# PX4Node_mini_V0_1_1.net
KiCad netlist of a schematic drawn in EAGLE
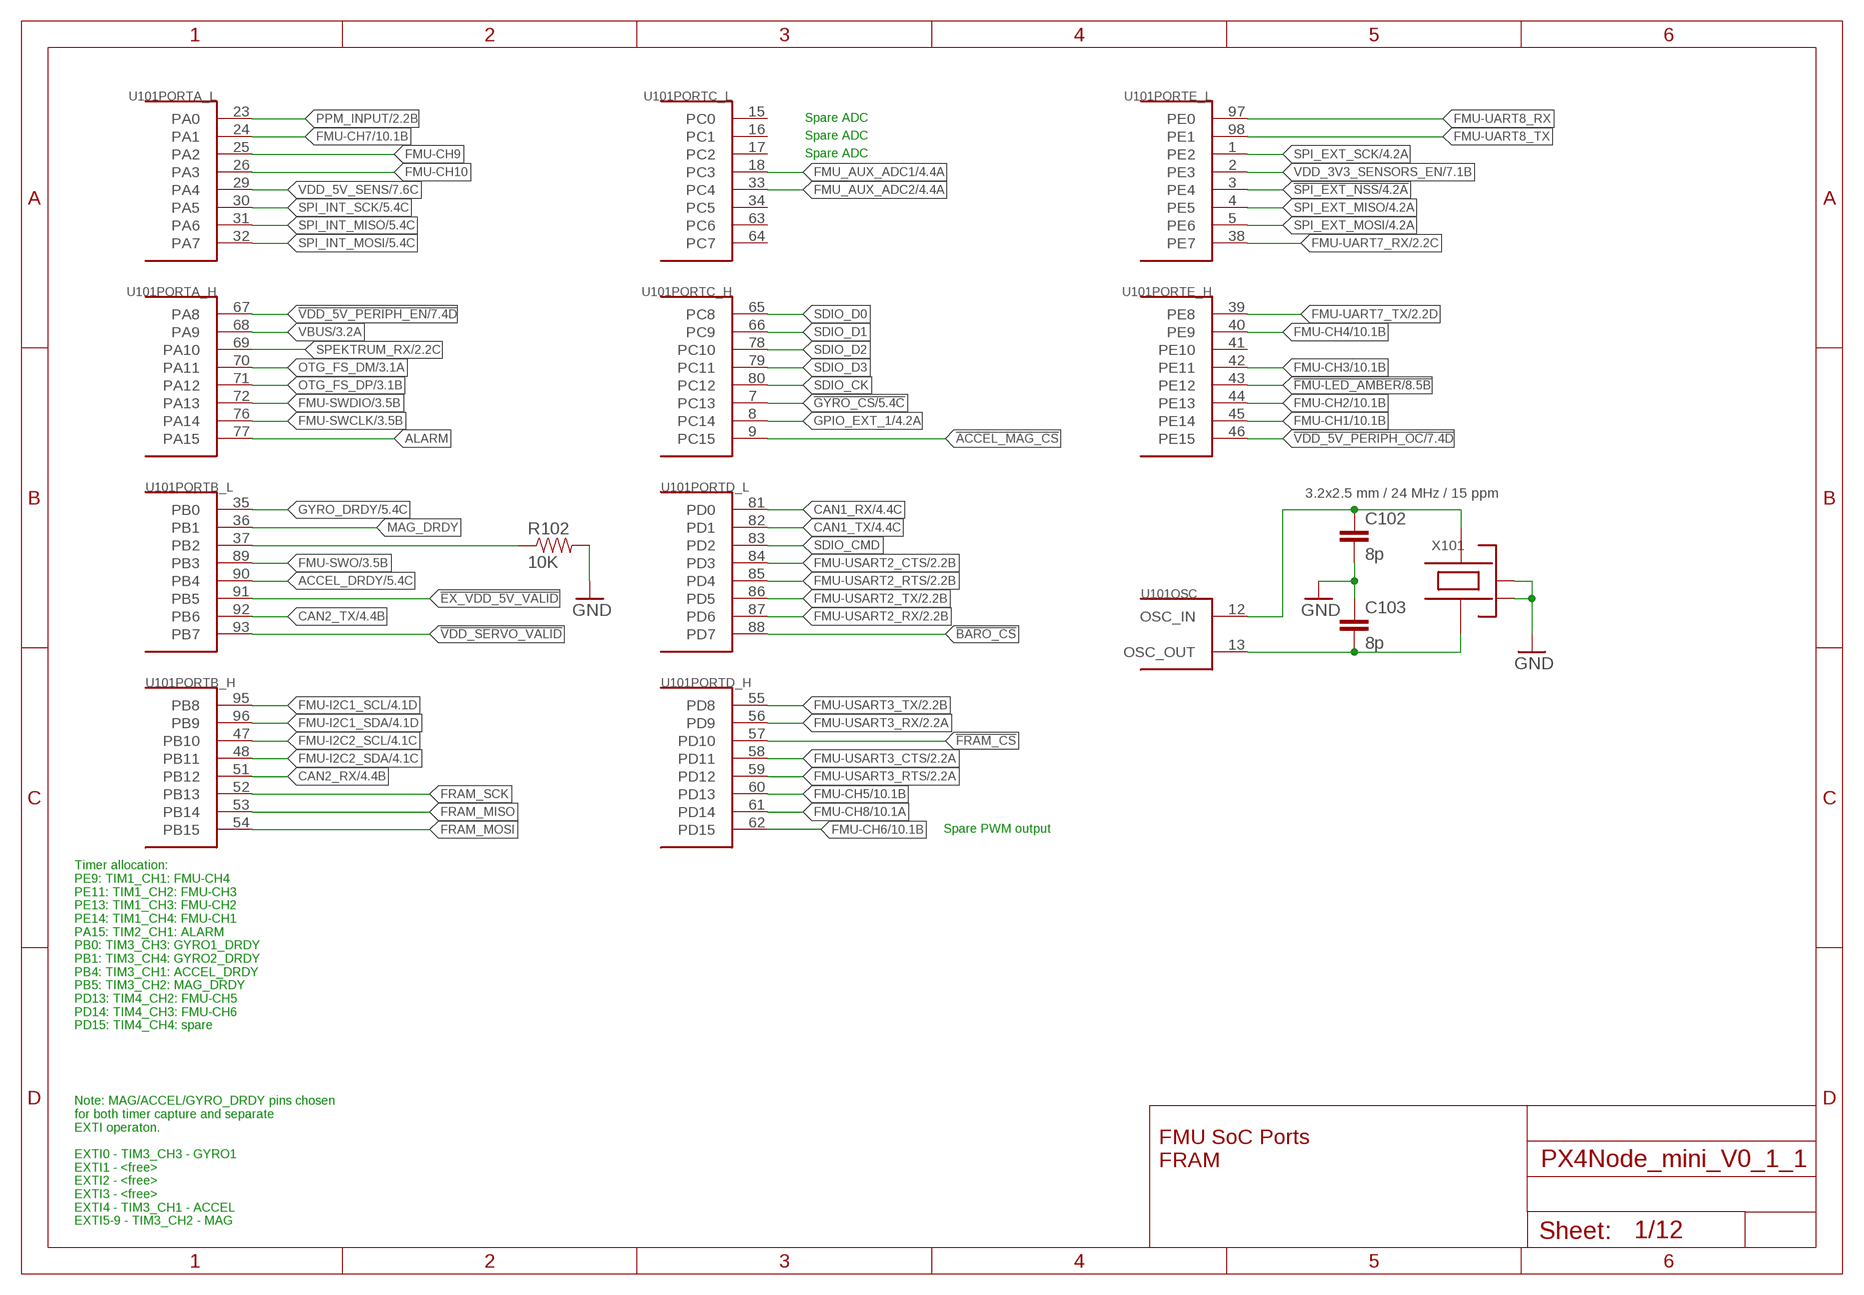
[diagram p0: schematic, sheet 1]
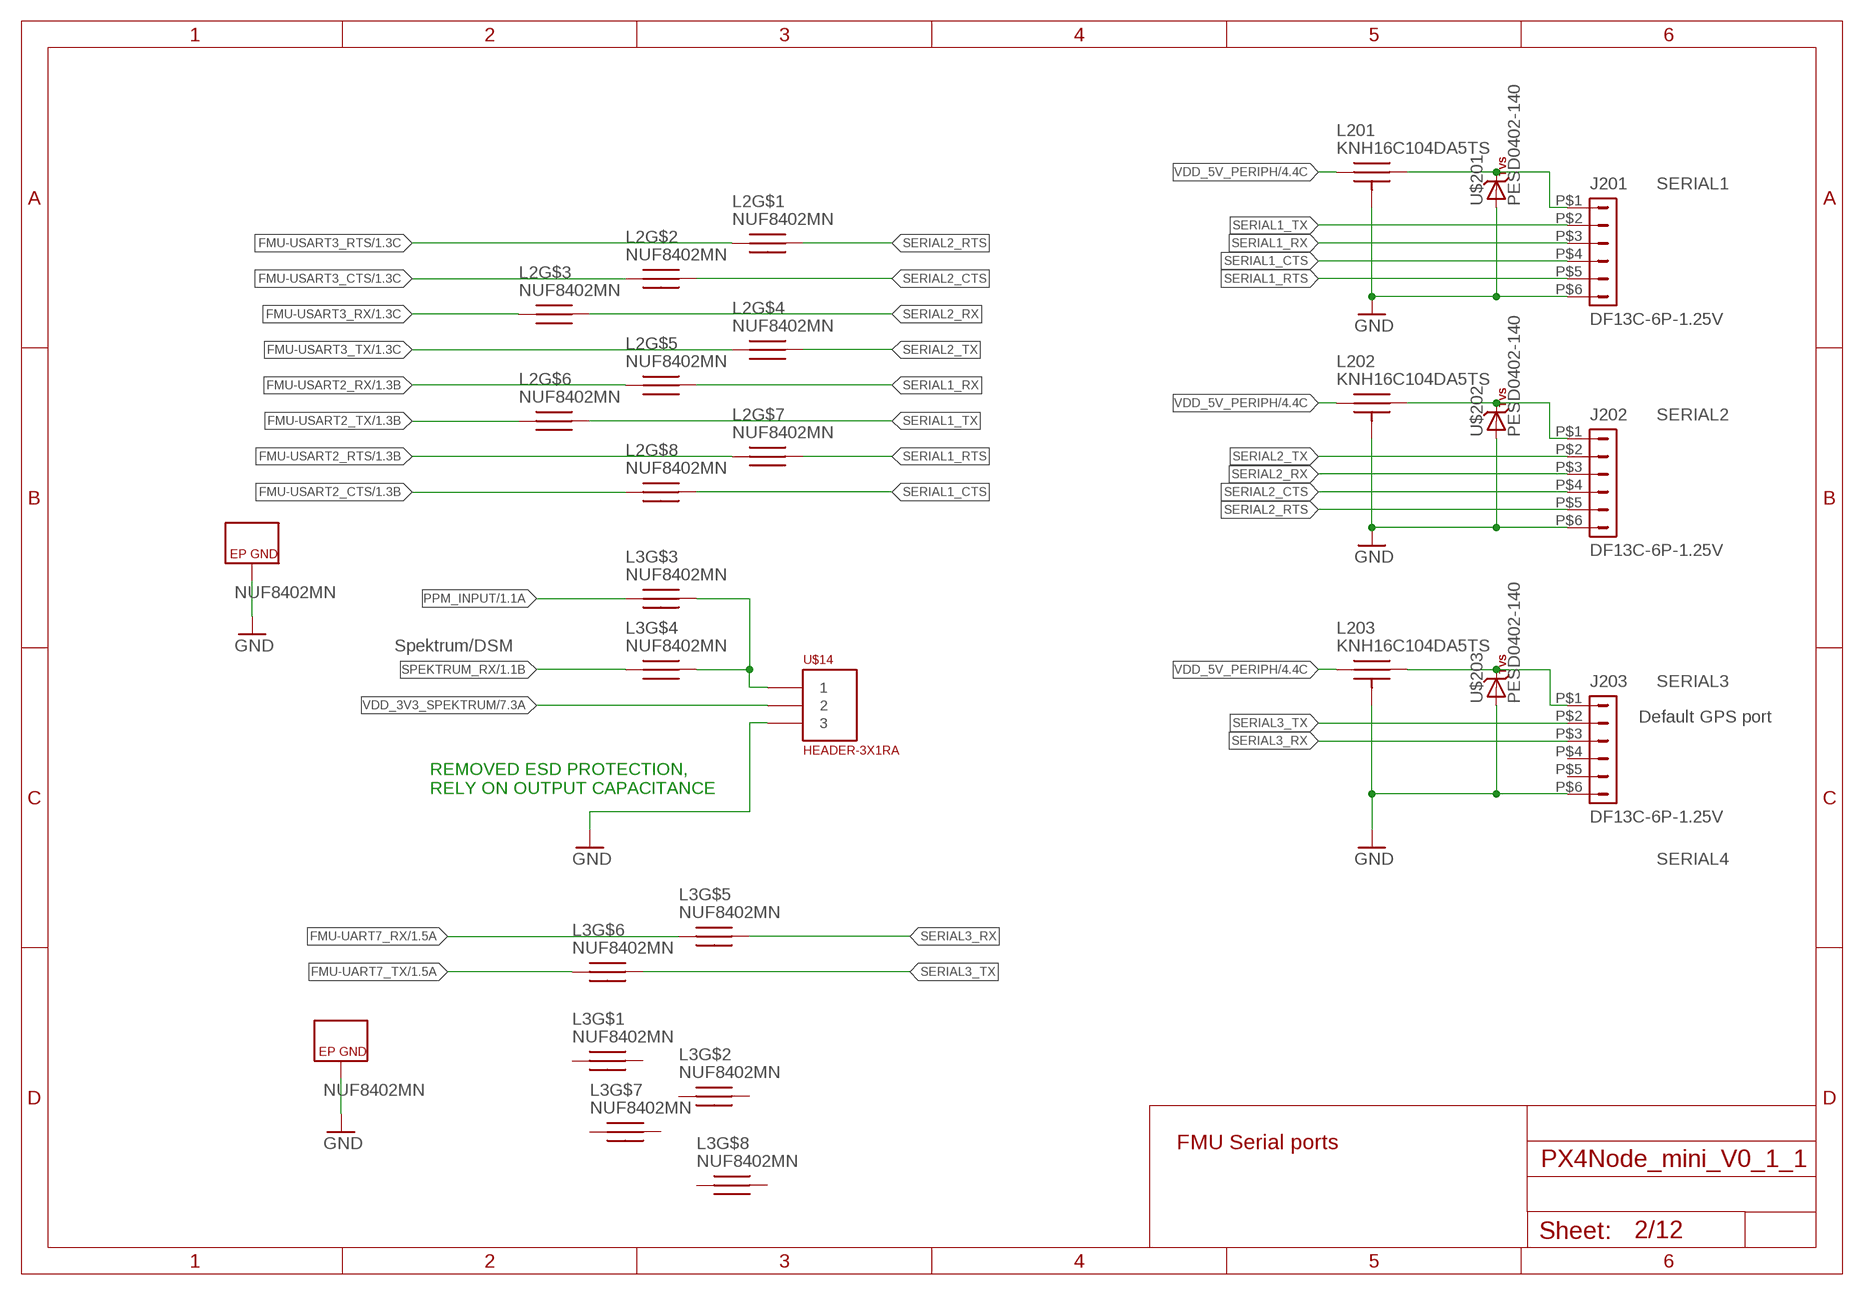
[diagram p1: schematic, sheet 2]
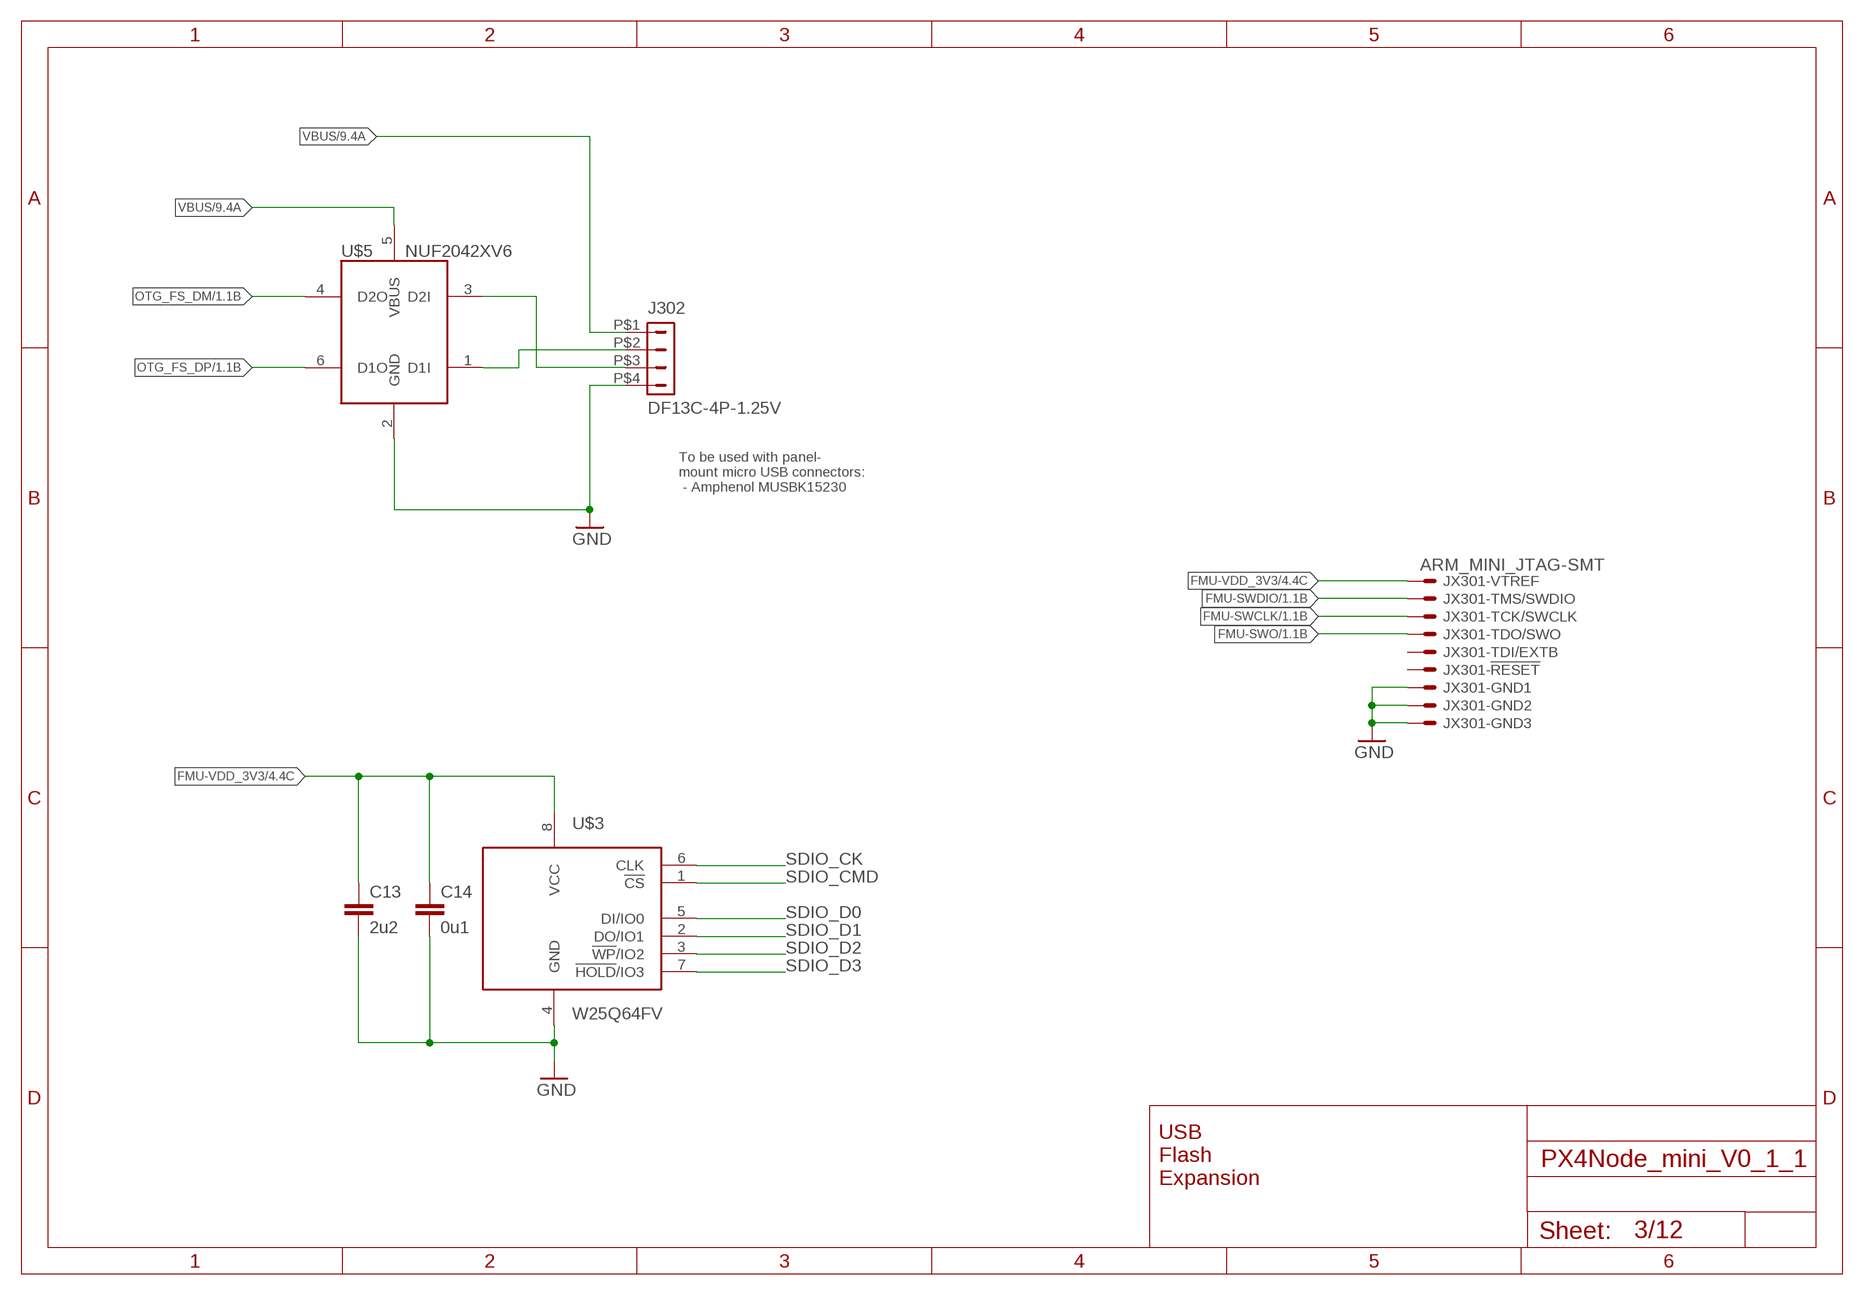
[diagram p2: schematic, sheet 3]
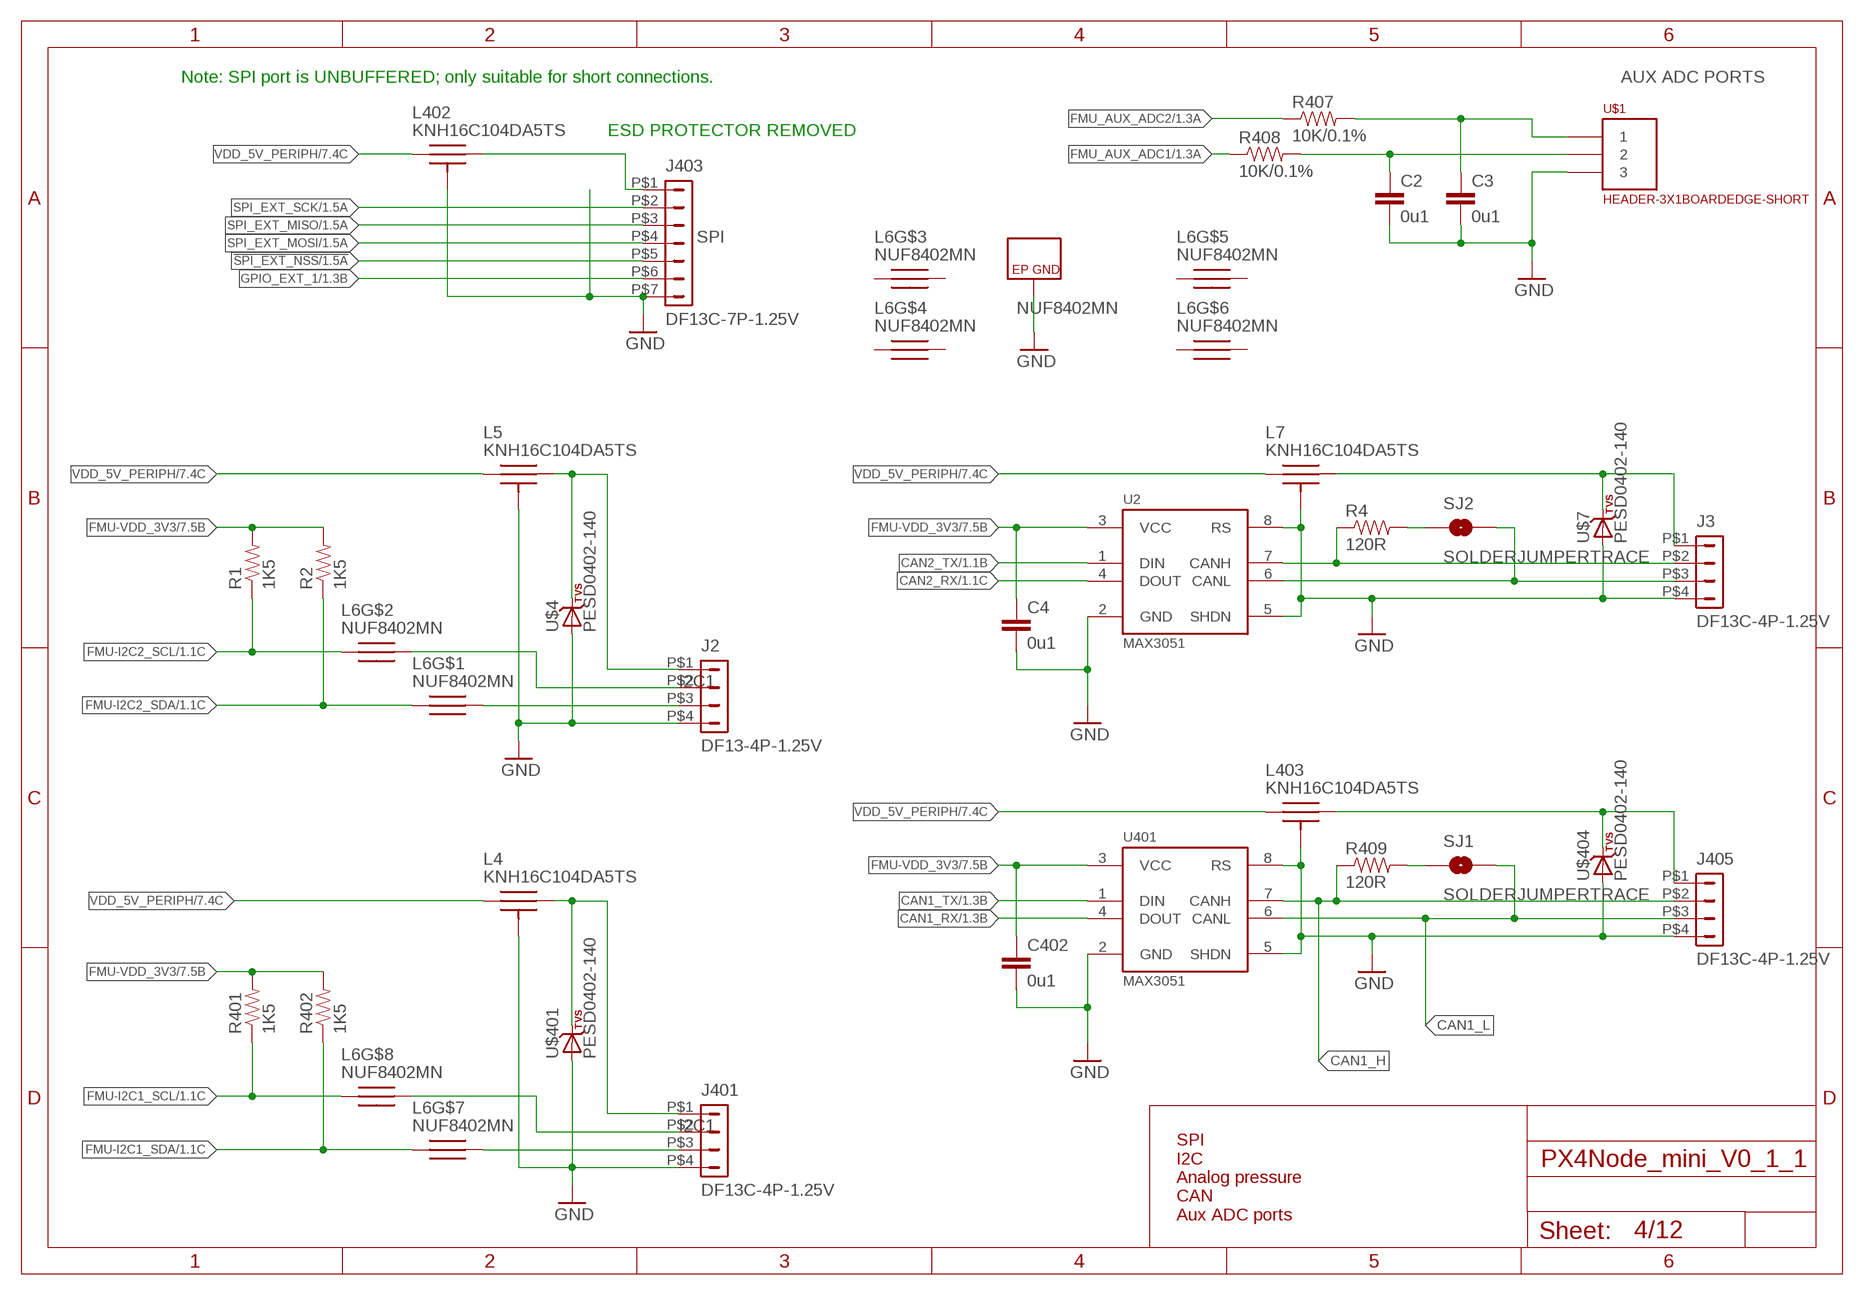
[diagram p3: schematic, sheet 4]
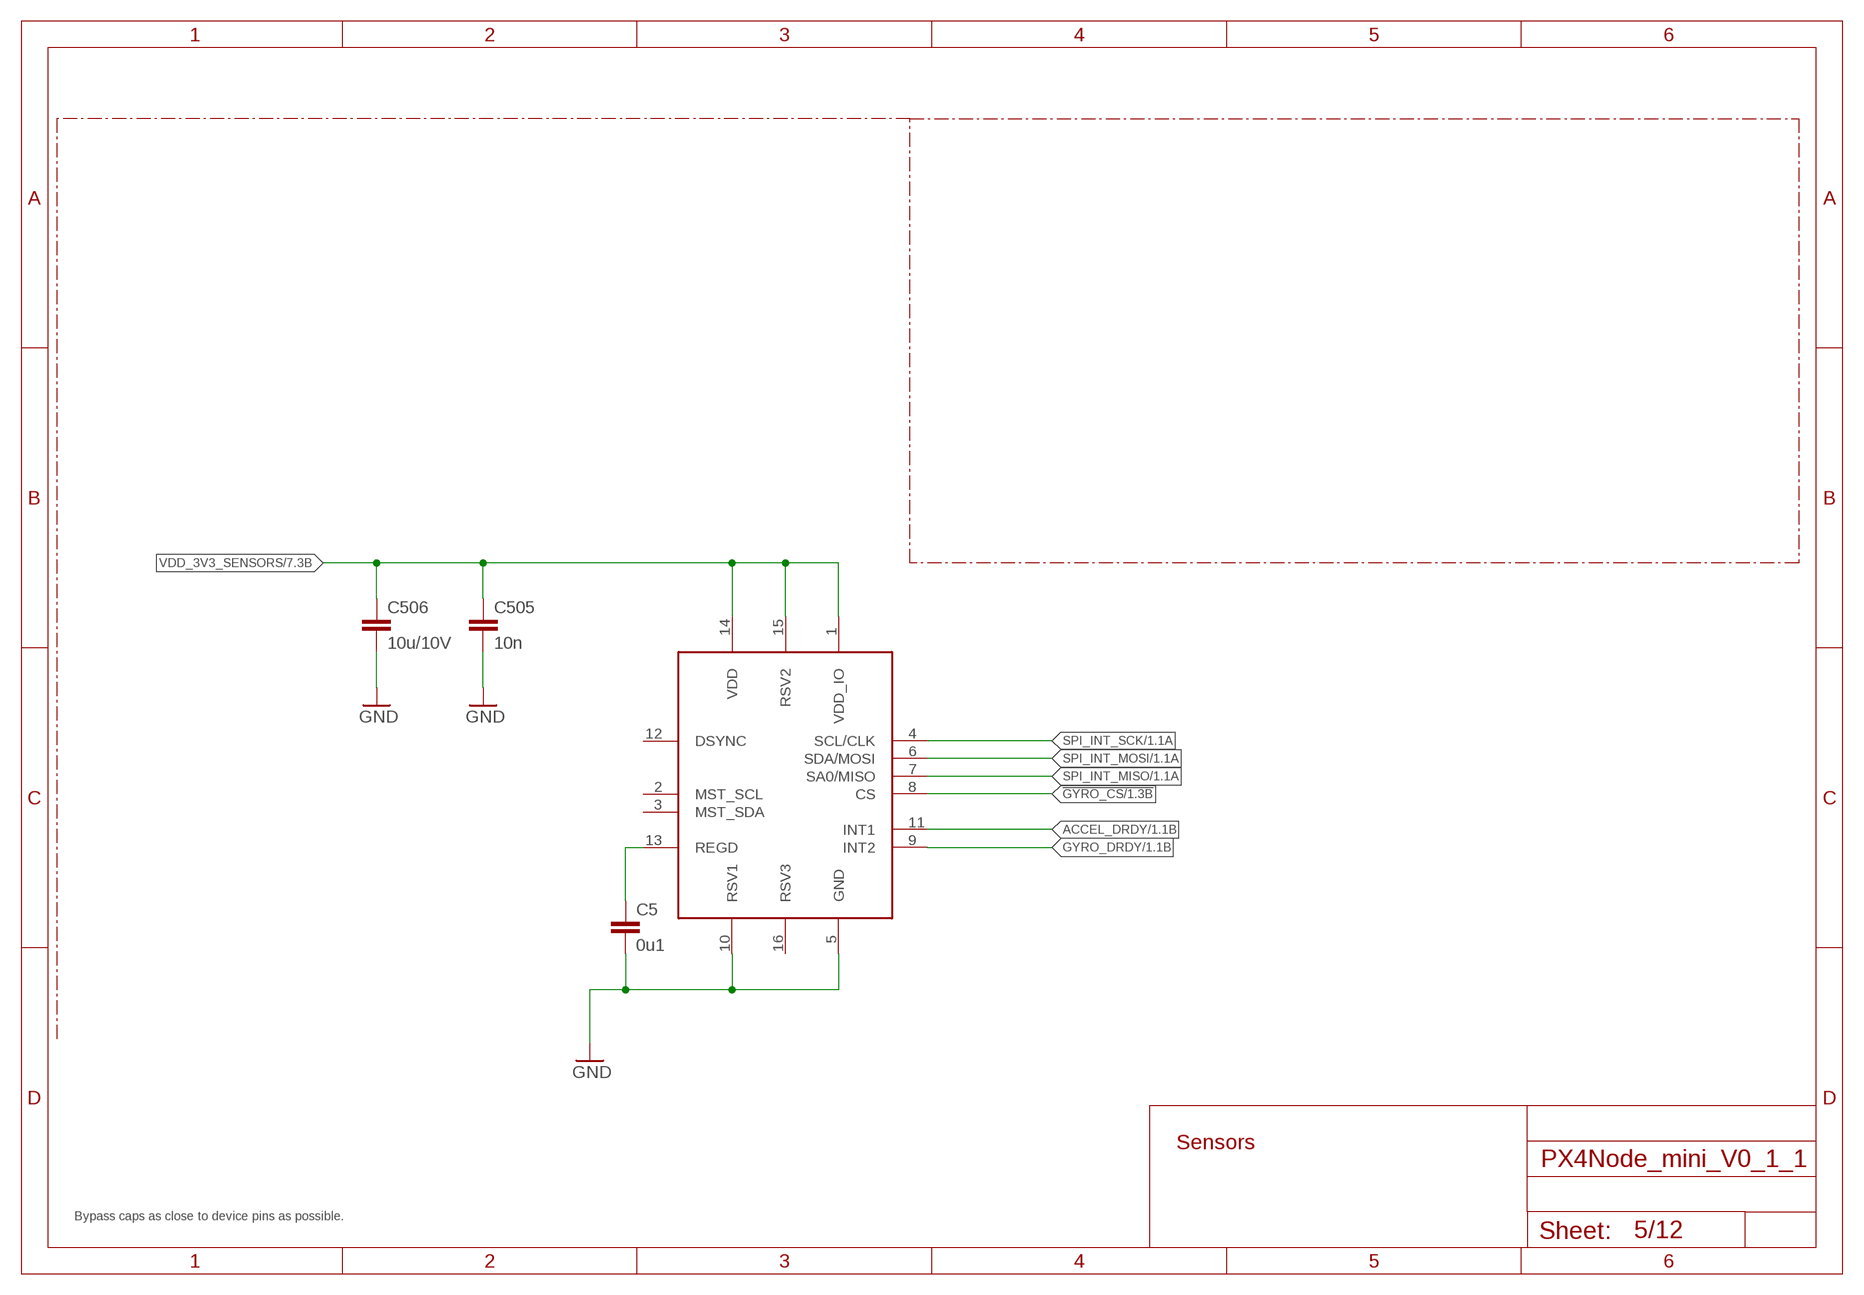
[diagram p4: schematic, sheet 5]
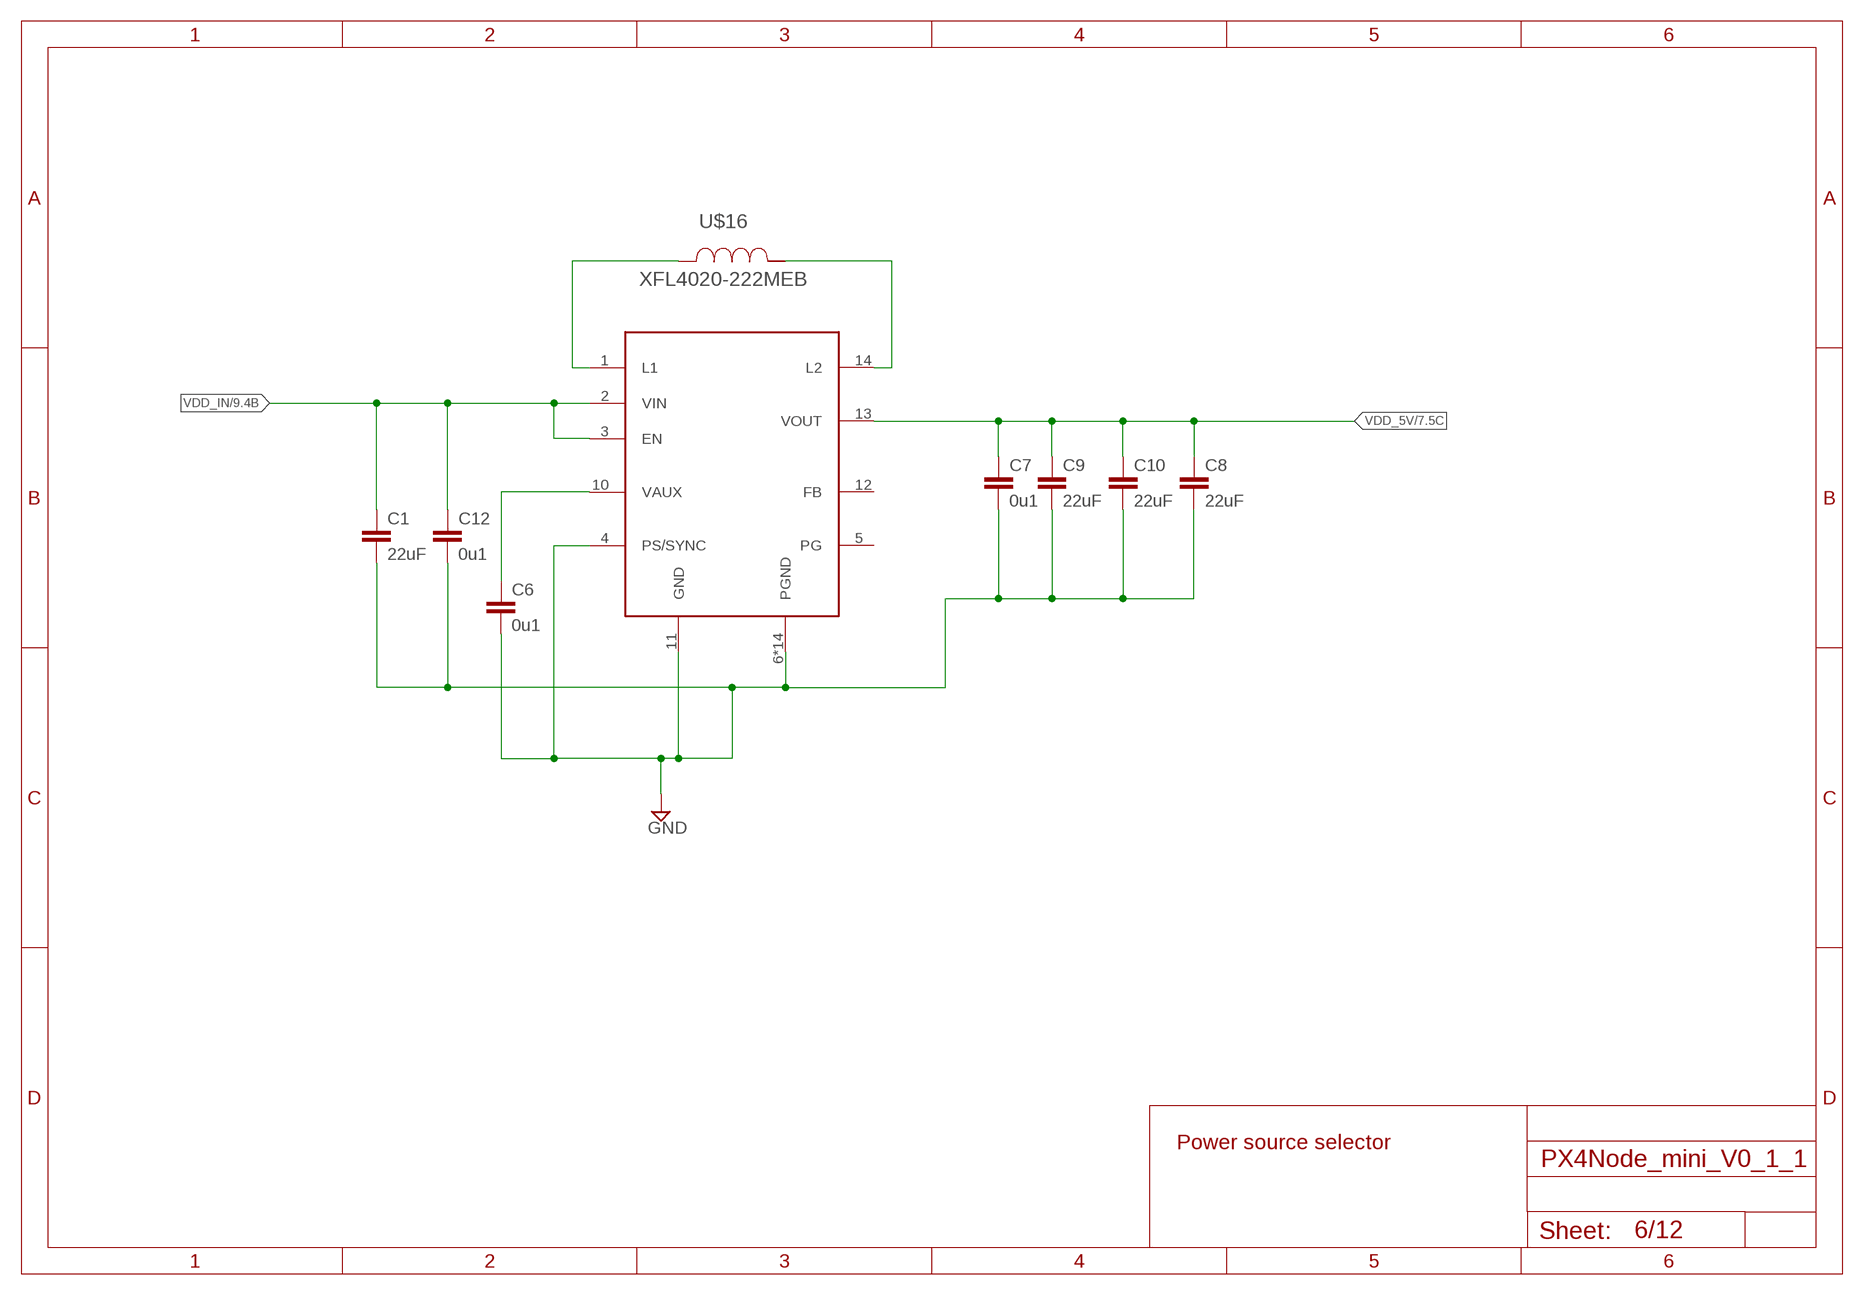
[diagram p5: schematic, sheet 6]
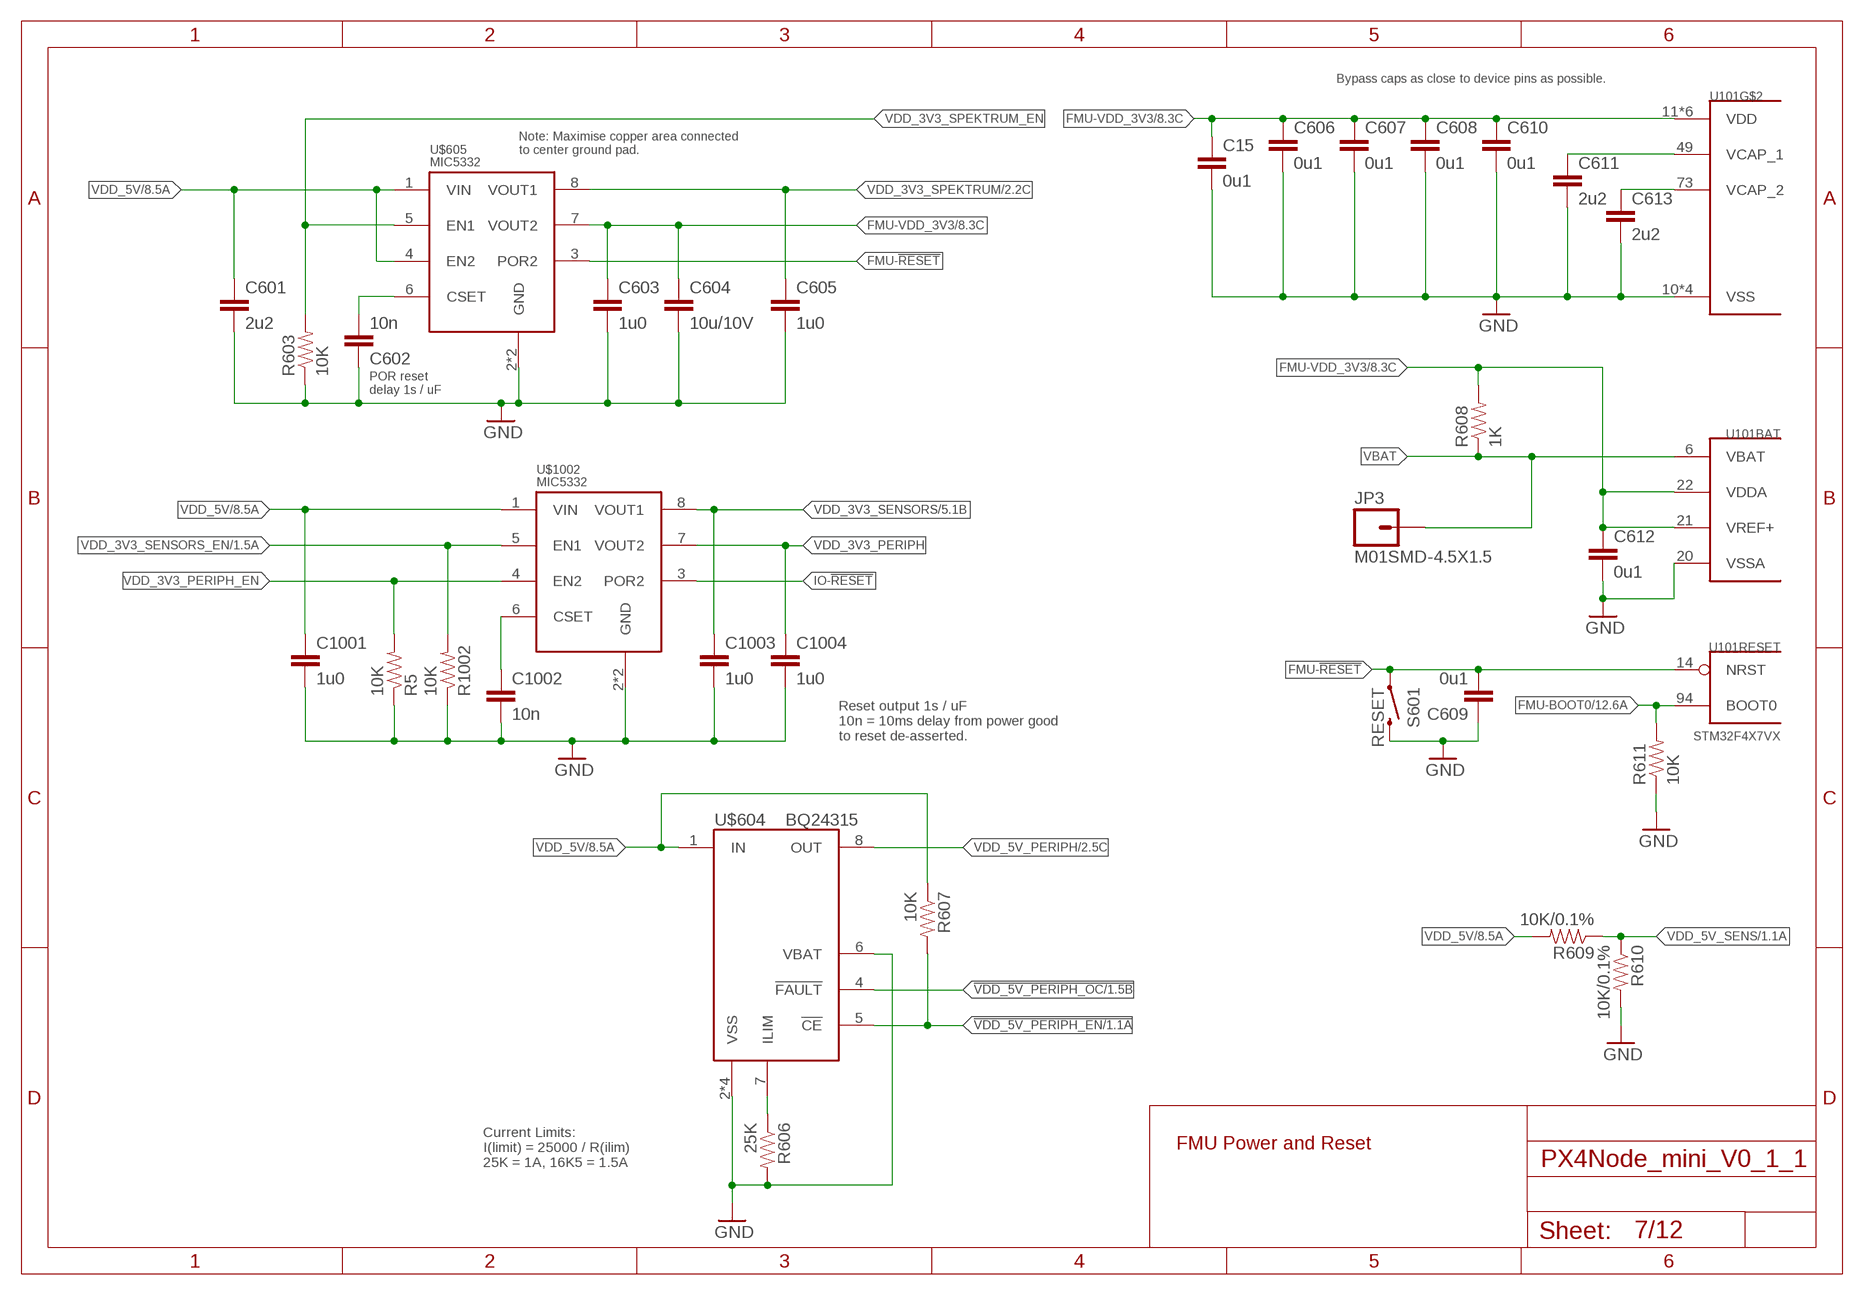
[diagram p6: schematic, sheet 7]
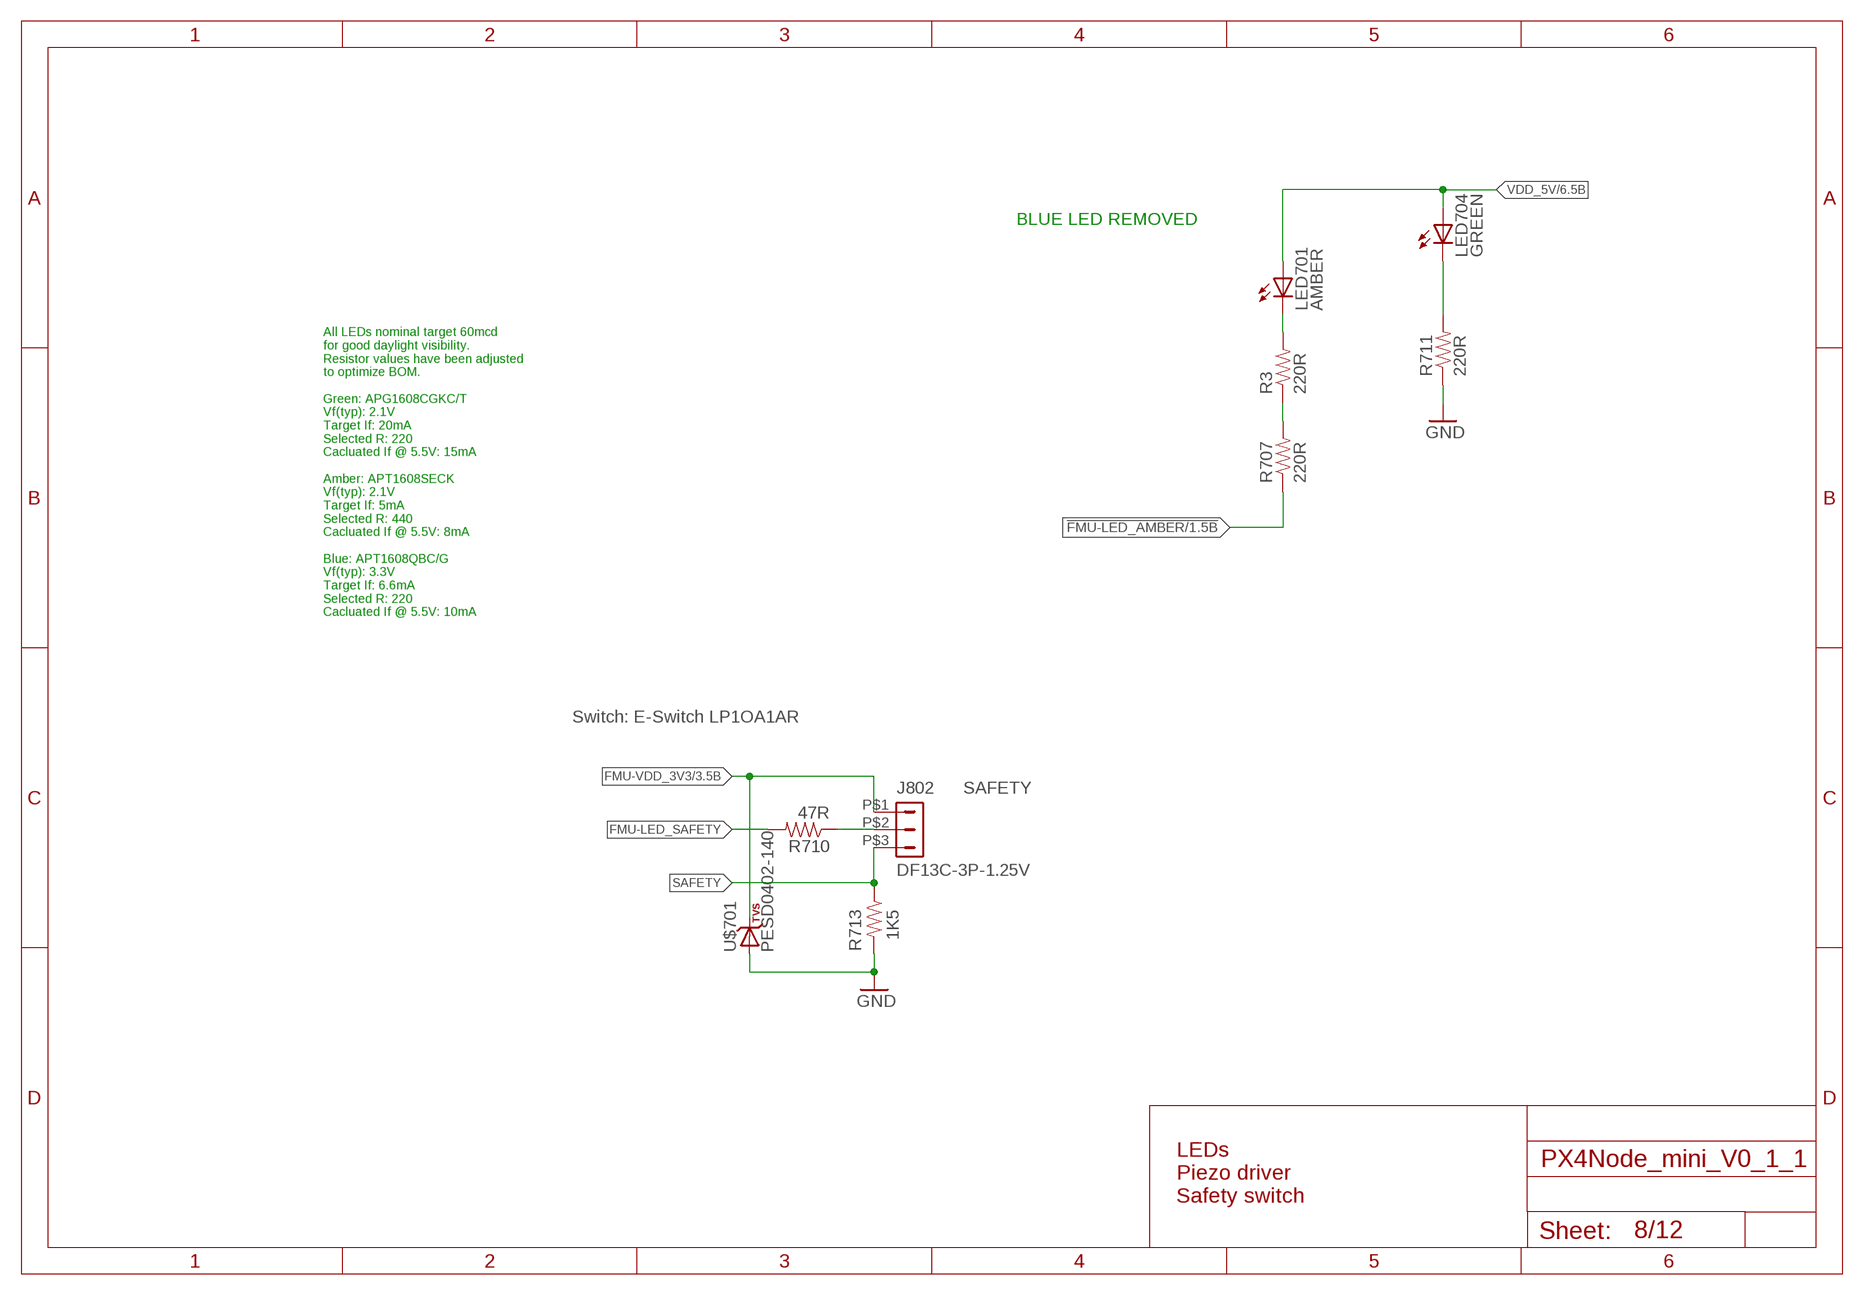
[diagram p7: schematic, sheet 8]
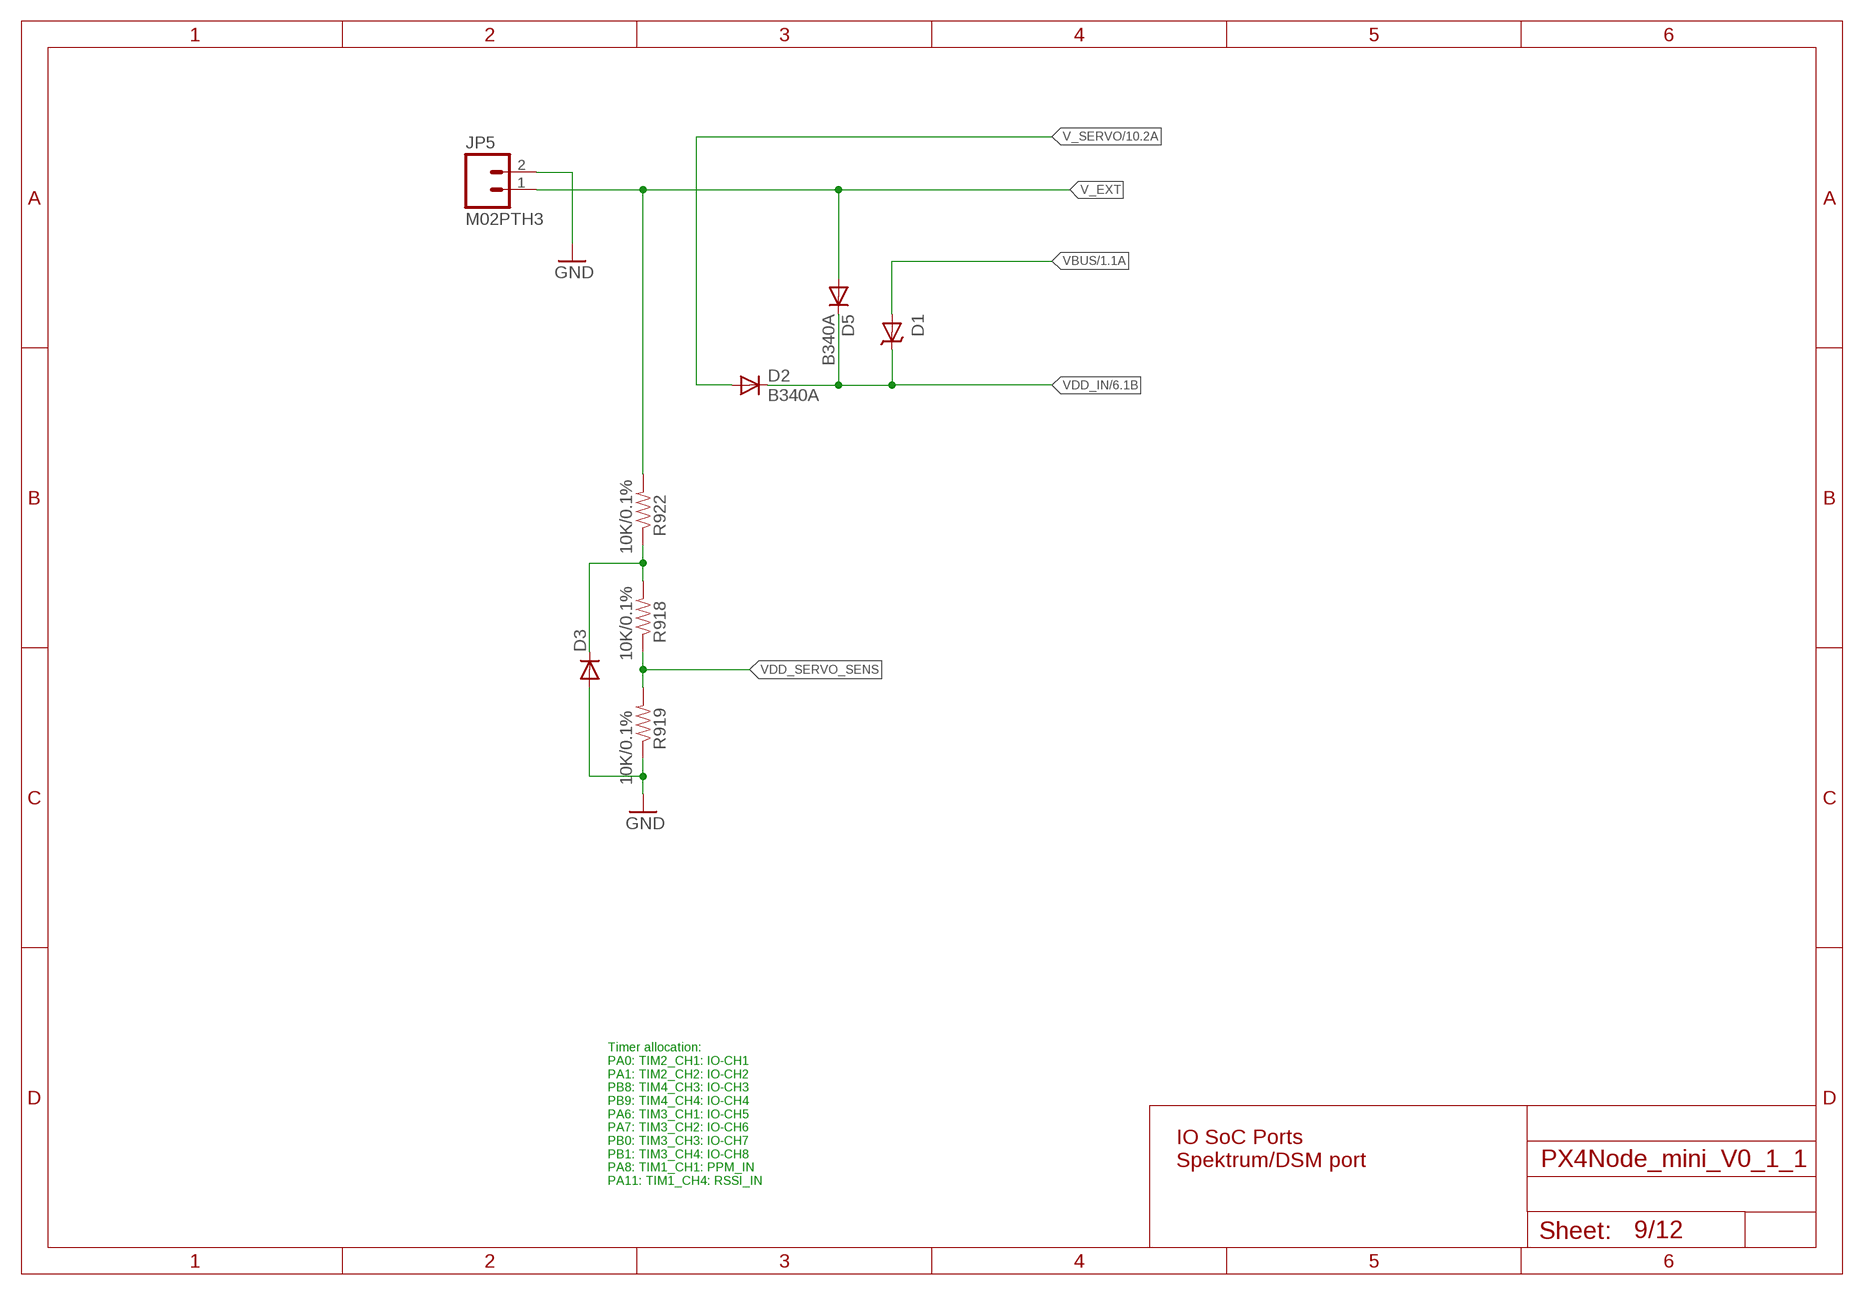
[diagram p8: schematic, sheet 9]
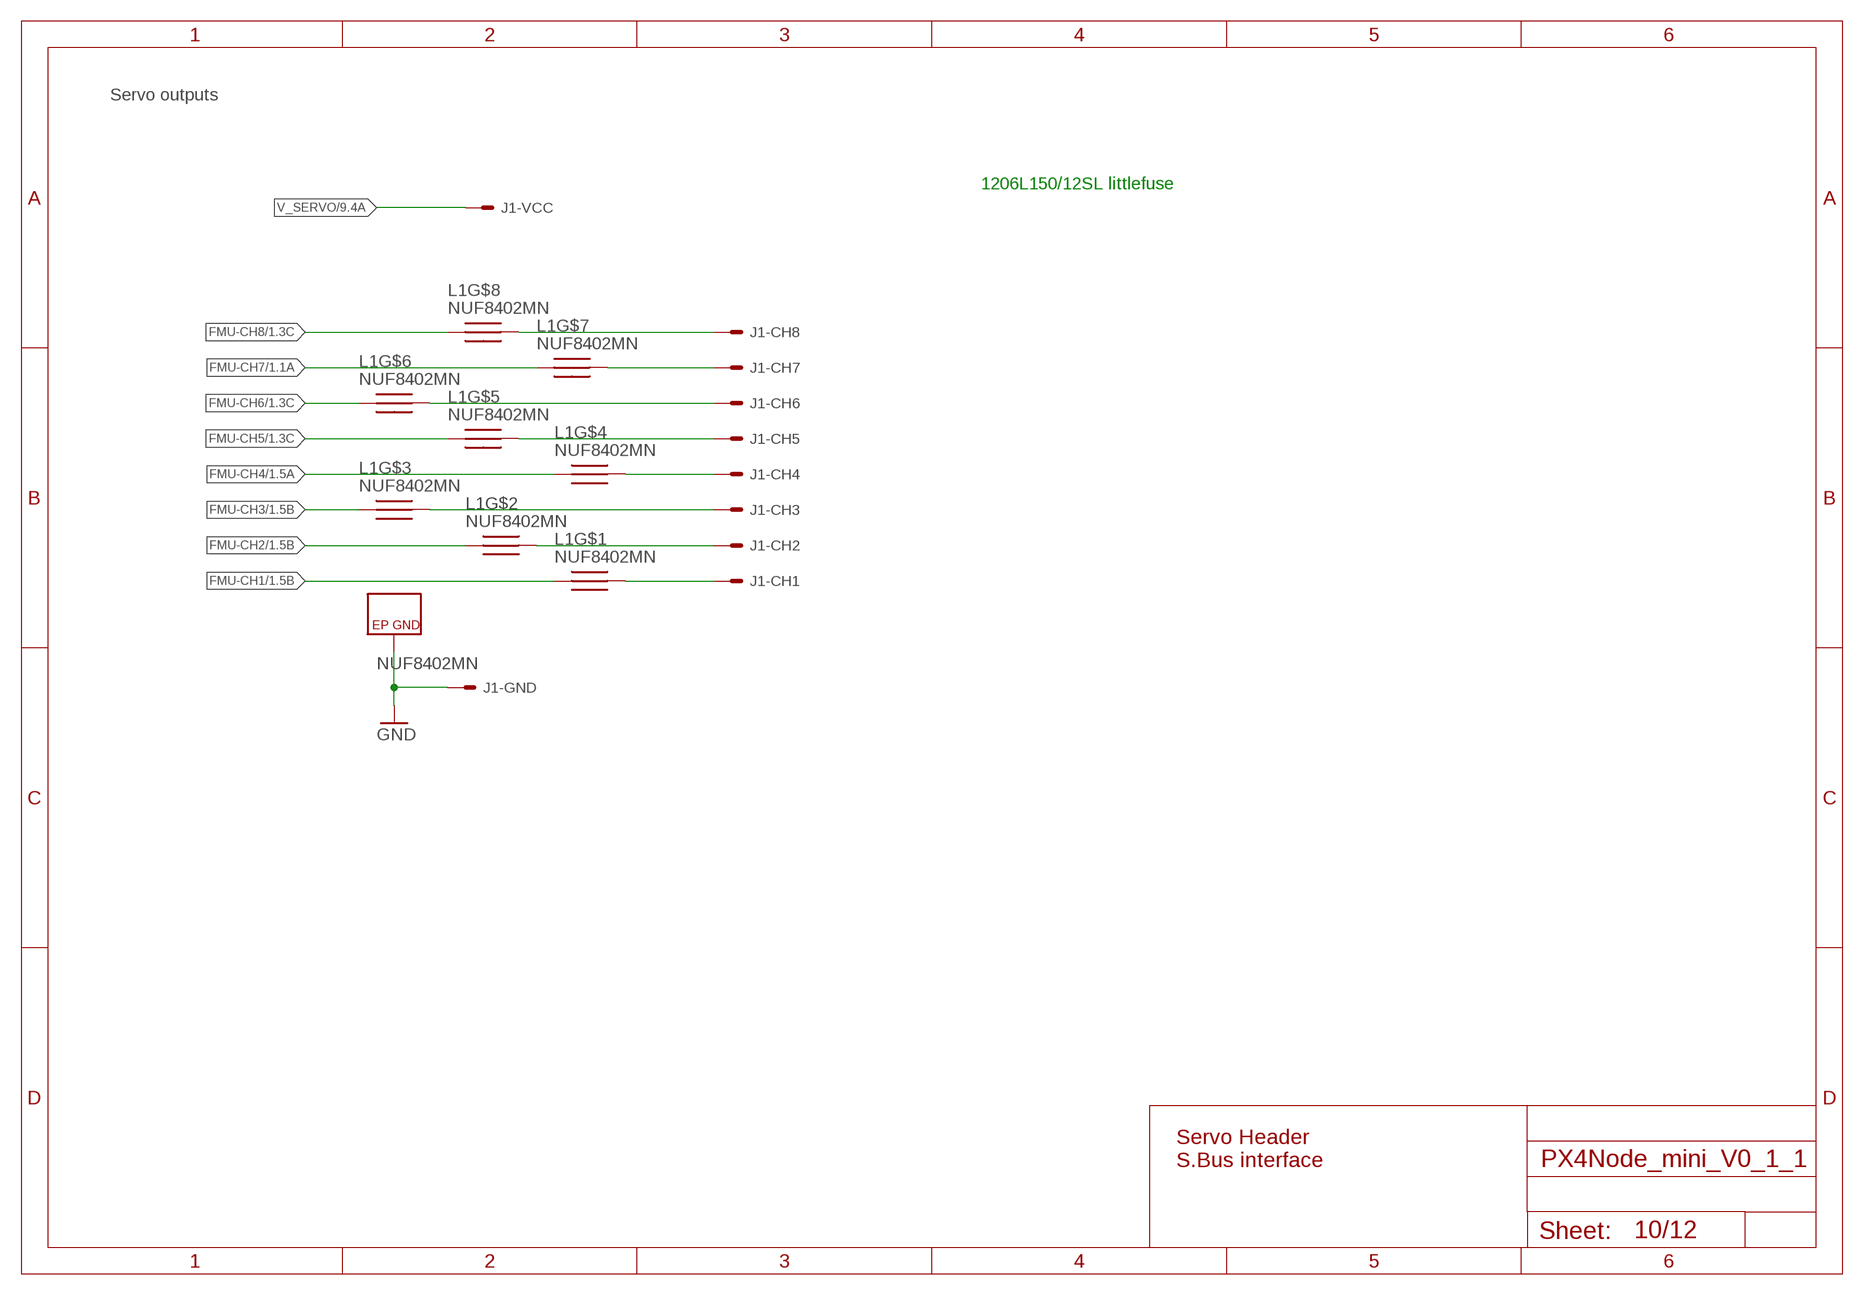
[diagram p9: schematic, sheet 10]
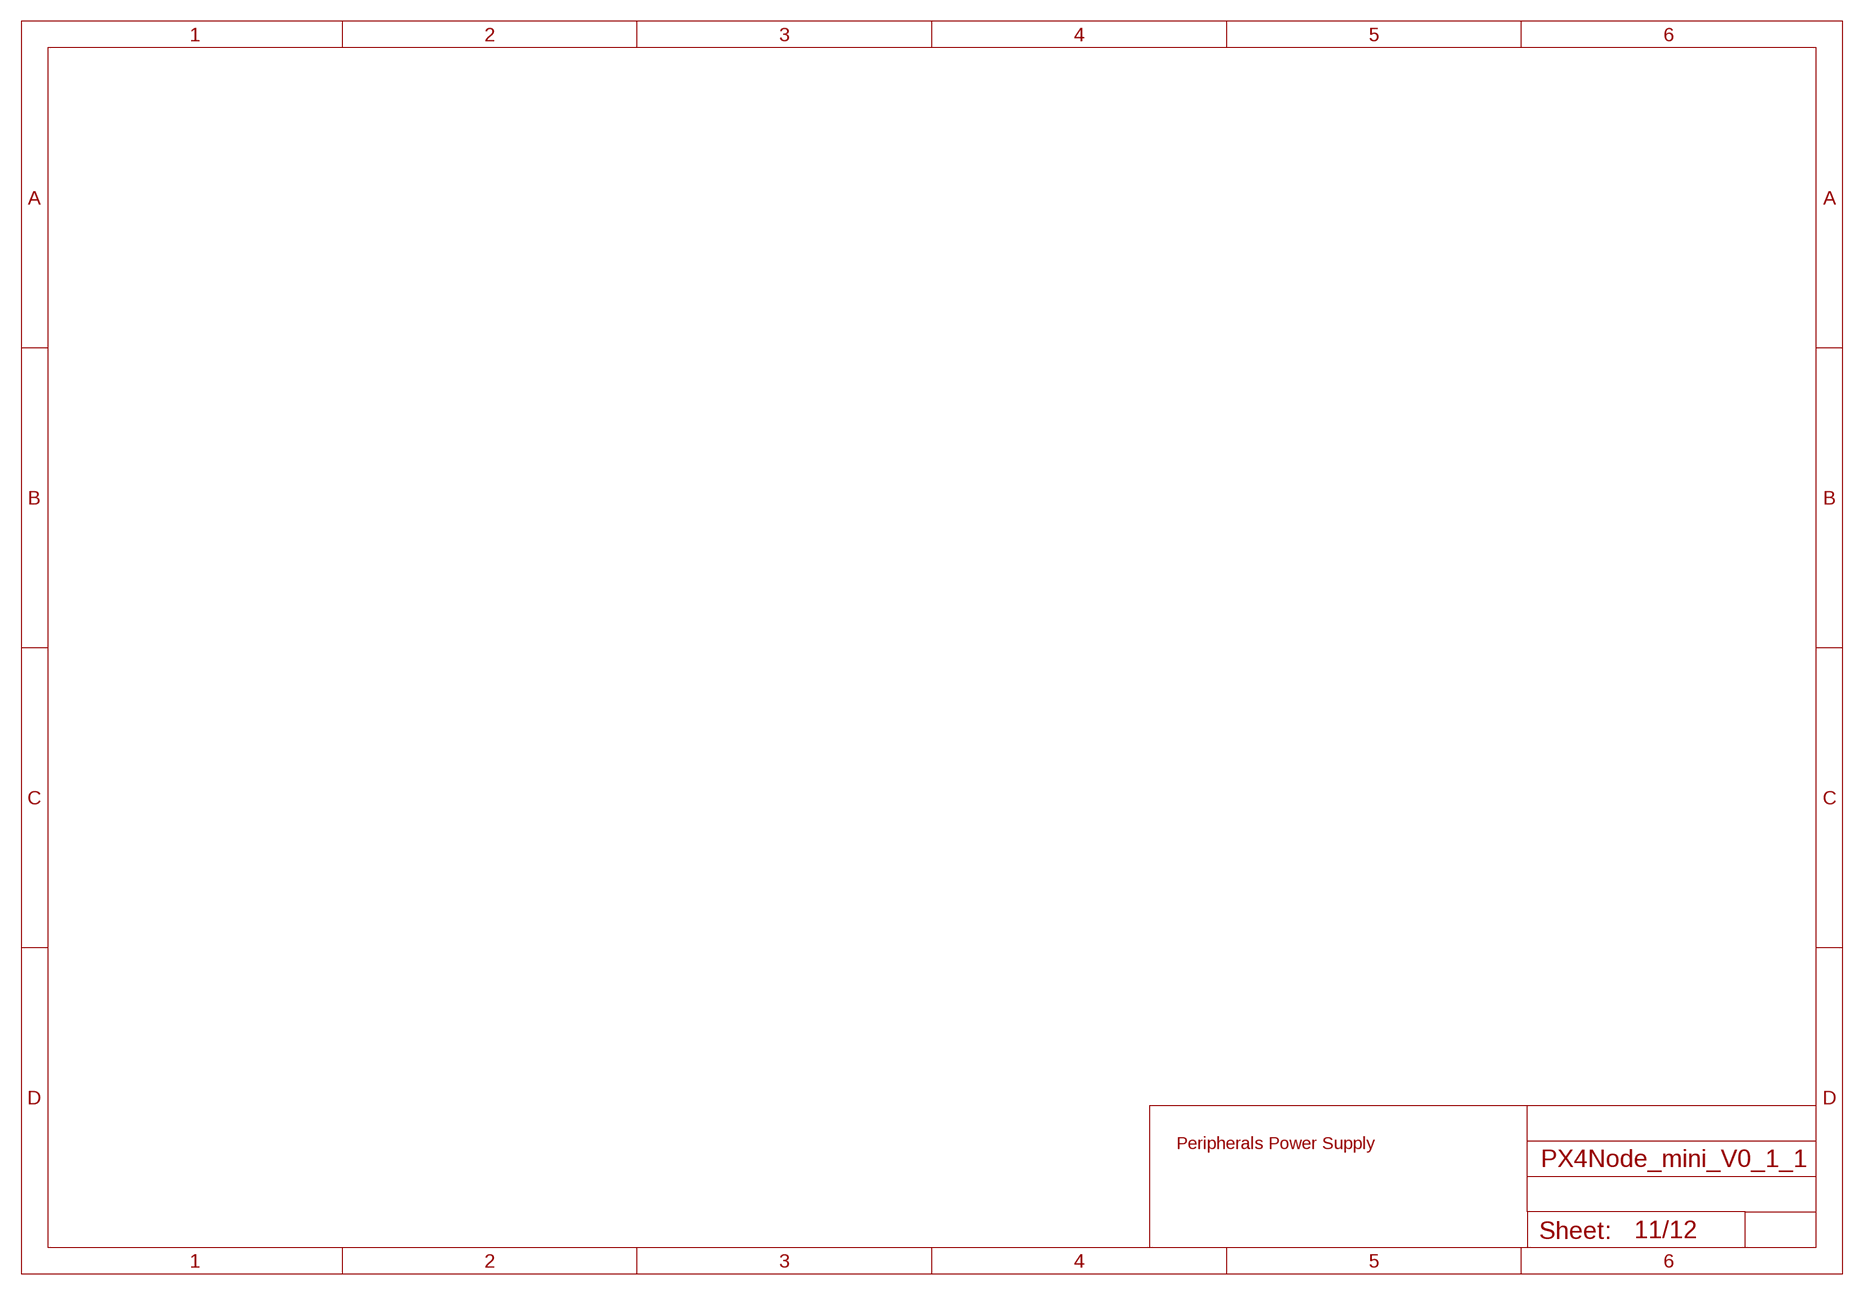
[diagram p10: schematic, sheet 11]
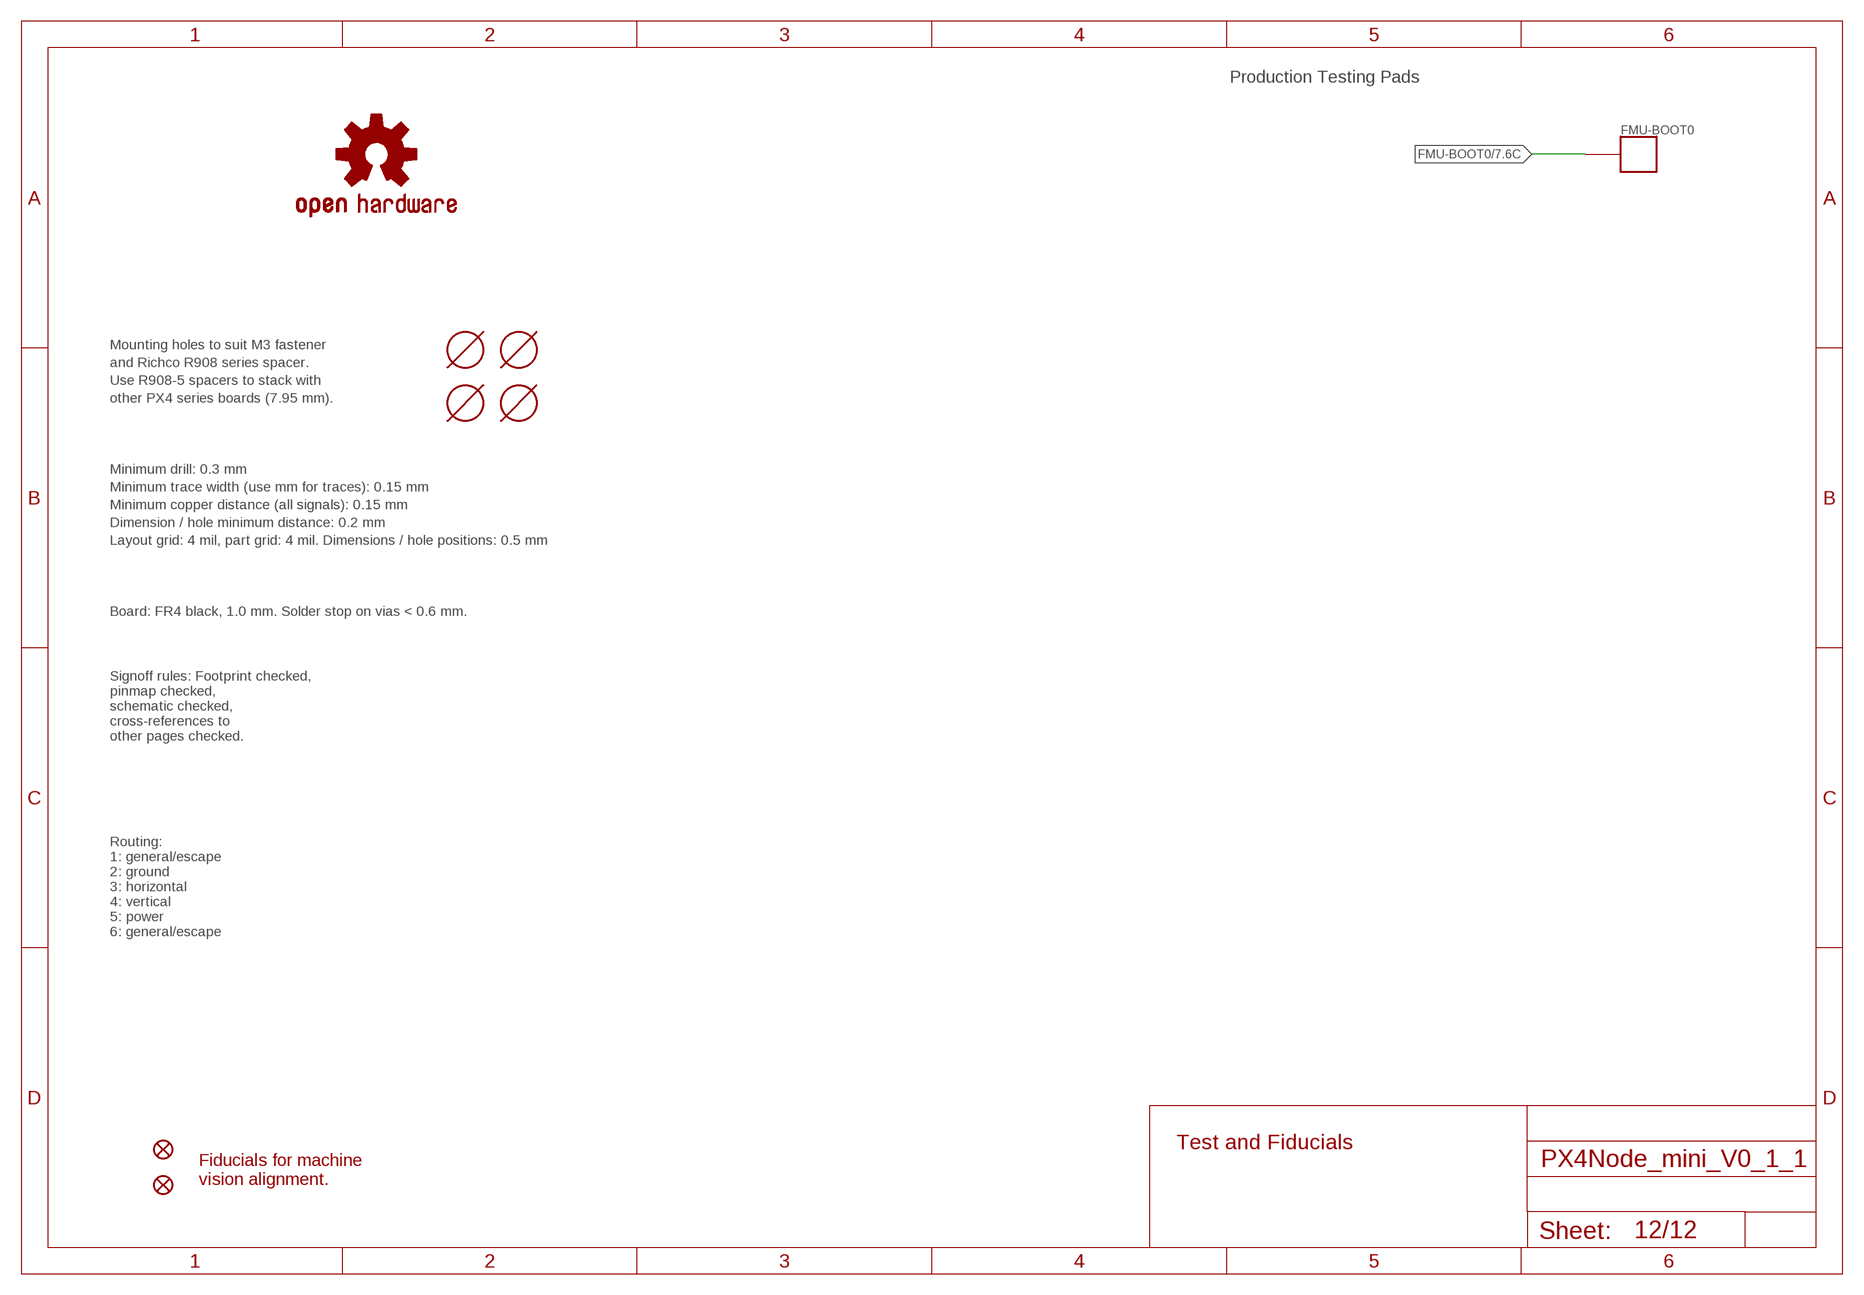
[diagram p11: schematic, sheet 12]

(export (version "E")
  (design (tool "Eeschema 10.0.6"))
  (components
    (comp (ref "C5")
      (value "0u1")
      (footprint "eagle-import:0402-CAP")
      (fields (field (name "PARTNO") "CC0402ZRY5V7BB104"))
      (libsource (lib "eagle-import") (part "CAP0402"))
    )
    (comp (ref "C505")
      (value "10n")
      (footprint "eagle-import:0402-CAP")
      (fields (field (name "PARTNO") "CC0402KRX7R7BB103"))
      (libsource (lib "eagle-import") (part "CAP0402"))
    )
    (comp (ref "C506")
      (value "10u/10V")
      (footprint "eagle-import:0805-CAP")
      (fields (field (name "PARTNO") "CC0805ZKY5V6BB106"))
      (libsource (lib "eagle-import") (part "CAP0805"))
    )
    (comp (ref "U$2")
      (value "MAX21100")
      (footprint "eagle-import:16LGA-3X3")
      (libsource (lib "eagle-import") (part "MAX21100"))
    )
    (comp (ref "C1")
      (value "22uF")
      (footprint "eagle-import:1210")
      (libsource (lib "eagle-import") (part "22UF-16V-20%-(1210)"))
    )
    (comp (ref "C6")
      (value "0u1")
      (footprint "eagle-import:0402-CAP")
      (fields (field (name "PARTNO") "CC0402ZRY5V7BB104"))
      (libsource (lib "eagle-import") (part "CAP0402"))
    )
    (comp (ref "C7")
      (value "0u1")
      (footprint "eagle-import:0402-CAP")
      (fields (field (name "PARTNO") "CC0402ZRY5V7BB104"))
      (libsource (lib "eagle-import") (part "CAP0402"))
    )
    (comp (ref "C8")
      (value "22uF")
      (footprint "eagle-import:1210")
      (libsource (lib "eagle-import") (part "22UF-16V-20%-(1210)"))
    )
    (comp (ref "C9")
      (value "22uF")
      (footprint "eagle-import:1210")
      (libsource (lib "eagle-import") (part "22UF-16V-20%-(1210)"))
    )
    (comp (ref "C10")
      (value "22uF")
      (footprint "eagle-import:1210")
      (libsource (lib "eagle-import") (part "22UF-16V-20%-(1210)"))
    )
    (comp (ref "C12")
      (value "0u1")
      (footprint "eagle-import:0402-CAP")
      (fields (field (name "PARTNO") "CC0402ZRY5V7BB104"))
      (libsource (lib "eagle-import") (part "CAP0402"))
    )
    (comp (ref "U$15")
      (value "TPS6303X")
      (footprint "eagle-import:PWSON10")
      (libsource (lib "eagle-import") (part "TPS6303X"))
    )
    (comp (ref "U$16")
      (value "XFL4020-222MEB")
      (footprint "eagle-import:XFL4020")
      (libsource (lib "eagle-import") (part "XFL4020-222MEB"))
    )
    (comp (ref "FMU-BOOT0")
      (value "PAD.04")
      (footprint "eagle-import:PAD.04X.04")
      (libsource (lib "eagle-import") (part "PAD.04"))
    )
    (comp (ref "JP1")
      (value "FIDUCIAL1.5X3")
      (footprint "eagle-import:FIDUCIAL-1.5X3")
      (libsource (lib "eagle-import") (part "FIDUCIAL1.5X3"))
    )
    (comp (ref "JP2")
      (value "FIDUCIAL1.5X3")
      (footprint "eagle-import:FIDUCIAL-1.5X3")
      (libsource (lib "eagle-import") (part "FIDUCIAL1.5X3"))
    )
    (comp (ref "M3_MOUNT1101")
      (value "MOUNT-HOLE3.1MM")
      (footprint "eagle-import:MOUNT-HOLE3.1")
      (libsource (lib "eagle-import") (part "MOUNT-HOLE3.1MM"))
    )
    (comp (ref "M3_MOUNT1102")
      (value "MOUNT-HOLE3.1MM")
      (footprint "eagle-import:MOUNT-HOLE3.1")
      (libsource (lib "eagle-import") (part "MOUNT-HOLE3.1MM"))
    )
    (comp (ref "M3_MOUNT1103")
      (value "MOUNT-HOLE3.1MM")
      (footprint "eagle-import:MOUNT-HOLE3.1")
      (libsource (lib "eagle-import") (part "MOUNT-HOLE3.1MM"))
    )
    (comp (ref "M3_MOUNT1104")
      (value "MOUNT-HOLE3.1MM")
      (footprint "eagle-import:MOUNT-HOLE3.1")
      (libsource (lib "eagle-import") (part "MOUNT-HOLE3.1MM"))
    )
    (comp (ref "OSHW_LOGO")
      (value "OSHW-LOGOS")
      (footprint "eagle-import:OSHW-LOGO-S")
      (libsource (lib "eagle-import") (part "OSHW-LOGOS"))
    )
    (comp (ref "C13")
      (value "2u2")
      (footprint "eagle-import:0603-CAP")
      (fields (field (name "PARTNO") "C1608Y5V1C225Z"))
      (libsource (lib "eagle-import") (part "CAP0603"))
    )
    (comp (ref "C14")
      (value "0u1")
      (footprint "eagle-import:0402-CAP")
      (fields (field (name "PARTNO") "CC0402ZRY5V7BB104"))
      (libsource (lib "eagle-import") (part "CAP0402"))
    )
    (comp (ref "J302")
      (value "DF13C-4P-1.25V")
      (footprint "eagle-import:DF13C-4P-1.25V")
      (fields (field (name "PARTNO") "DF13C-4P-1.25V(20)"))
      (libsource (lib "eagle-import") (part "DF13-4P-1.25V"))
    )
    (comp (ref "JX301")
      (value "ARM_MINI_JTAG-SMT")
      (footprint "eagle-import:FTSH-105-01-XXX-DV-K")
      (fields (field (name "BOM") "EXCLUDE") (field (name "PARTNO") "M50-3900542"))
      (libsource (lib "eagle-import") (part "ARM_MINI_JTAG-SMT"))
    )
    (comp (ref "U$3")
      (value "W25Q64FV")
      (footprint "eagle-import:WSON-8-5X6")
      (libsource (lib "eagle-import") (part "W25Q64FV"))
    )
    (comp (ref "U$5")
      (value "NUF2042XV6")
      (footprint "eagle-import:SOT563-6")
      (libsource (lib "eagle-import") (part "NUF2042XV6"))
    )
    (comp (ref "J201")
      (value "DF13C-6P-1.25V")
      (footprint "eagle-import:DF13C-6P-1.25V")
      (fields (field (name "PARTNO") "DF13C-6P-1.25V(20)"))
      (libsource (lib "eagle-import") (part "DF13-6P-1.25V"))
    )
    (comp (ref "J202")
      (value "DF13C-6P-1.25V")
      (footprint "eagle-import:DF13C-6P-1.25V")
      (fields (field (name "PARTNO") "DF13C-6P-1.25V(20)"))
      (libsource (lib "eagle-import") (part "DF13-6P-1.25V"))
    )
    (comp (ref "J203")
      (value "DF13C-6P-1.25V")
      (footprint "eagle-import:DF13C-6P-1.25V")
      (fields (field (name "PARTNO") "DF13C-6P-1.25V(20)"))
      (libsource (lib "eagle-import") (part "DF13-6P-1.25V"))
    )
    (comp (ref "L2")
      (value "NUF8402MN")
      (footprint "eagle-import:DFN16-THIN")
      (libsource (lib "eagle-import") (part "NUF8402MN"))
    )
    (comp (ref "L3")
      (value "NUF8402MN")
      (footprint "eagle-import:DFN16-THIN")
      (libsource (lib "eagle-import") (part "NUF8402MN"))
    )
    (comp (ref "L201")
      (value "KNH16C104DA5TS")
      (footprint "eagle-import:KYOCERA-KNH16-DA")
      (libsource (lib "eagle-import") (part "KNH16C104DA5TS"))
    )
    (comp (ref "L202")
      (value "KNH16C104DA5TS")
      (footprint "eagle-import:KYOCERA-KNH16-DA")
      (libsource (lib "eagle-import") (part "KNH16C104DA5TS"))
    )
    (comp (ref "L203")
      (value "KNH16C104DA5TS")
      (footprint "eagle-import:KYOCERA-KNH16-DA")
      (libsource (lib "eagle-import") (part "KNH16C104DA5TS"))
    )
    (comp (ref "U$14")
      (value "HEADER-3X1RA")
      (footprint "eagle-import:3X1RA")
      (libsource (lib "eagle-import") (part "HEADER-3X1RA"))
    )
    (comp (ref "U$201")
      (value "PESD0402-140")
      (footprint "eagle-import:0402-TVS")
      (libsource (lib "eagle-import") (part "DIODE-TVS"))
    )
    (comp (ref "U$202")
      (value "PESD0402-140")
      (footprint "eagle-import:0402-TVS")
      (libsource (lib "eagle-import") (part "DIODE-TVS"))
    )
    (comp (ref "U$203")
      (value "PESD0402-140")
      (footprint "eagle-import:0402-TVS")
      (libsource (lib "eagle-import") (part "DIODE-TVS"))
    )
    (comp (ref "C15")
      (value "0u1")
      (footprint "eagle-import:0402-CAP")
      (fields (field (name "PARTNO") "CC0402ZRY5V7BB104"))
      (libsource (lib "eagle-import") (part "CAP0402"))
    )
    (comp (ref "C601")
      (value "2u2")
      (footprint "eagle-import:0603-CAP")
      (fields (field (name "PARTNO") "C1608Y5V1C225Z"))
      (libsource (lib "eagle-import") (part "CAP0603"))
    )
    (comp (ref "C602")
      (value "10n")
      (footprint "eagle-import:0402-CAP")
      (fields (field (name "PARTNO") "CC0402KRX7R7BB103"))
      (libsource (lib "eagle-import") (part "CAP0402"))
    )
    (comp (ref "C603")
      (value "1u0")
      (footprint "eagle-import:0603-CAP")
      (fields (field (name "PARTNO") "CC0603ZRY5V7BB105"))
      (libsource (lib "eagle-import") (part "CAP0603"))
    )
    (comp (ref "C604")
      (value "10u/10V")
      (footprint "eagle-import:0805-CAP")
      (fields (field (name "PARTNO") "CC0805ZKY5V6BB106"))
      (libsource (lib "eagle-import") (part "CAP0805"))
    )
    (comp (ref "C605")
      (value "1u0")
      (footprint "eagle-import:0603-CAP")
      (fields (field (name "PARTNO") "CC0603ZRY5V7BB105"))
      (libsource (lib "eagle-import") (part "CAP0603"))
    )
    (comp (ref "C606")
      (value "0u1")
      (footprint "eagle-import:0402-CAP")
      (fields (field (name "PARTNO") "CC0402ZRY5V7BB104"))
      (libsource (lib "eagle-import") (part "CAP0402"))
    )
    (comp (ref "C607")
      (value "0u1")
      (footprint "eagle-import:0402-CAP")
      (fields (field (name "PARTNO") "CC0402ZRY5V7BB104"))
      (libsource (lib "eagle-import") (part "CAP0402"))
    )
    (comp (ref "C608")
      (value "0u1")
      (footprint "eagle-import:0402-CAP")
      (fields (field (name "PARTNO") "CC0402ZRY5V7BB104"))
      (libsource (lib "eagle-import") (part "CAP0402"))
    )
    (comp (ref "C609")
      (value "0u1")
      (footprint "eagle-import:0402-CAP")
      (fields (field (name "PARTNO") "CC0402ZRY5V7BB104"))
      (libsource (lib "eagle-import") (part "CAP0402"))
    )
    (comp (ref "C610")
      (value "0u1")
      (footprint "eagle-import:0402-CAP")
      (fields (field (name "PARTNO") "CC0402ZRY5V7BB104"))
      (libsource (lib "eagle-import") (part "CAP0402"))
    )
    (comp (ref "C611")
      (value "2u2")
      (footprint "eagle-import:0603-CAP")
      (fields (field (name "PARTNO") "C1608Y5V1C225Z"))
      (libsource (lib "eagle-import") (part "CAP0603"))
    )
    (comp (ref "C612")
      (value "0u1")
      (footprint "eagle-import:0402-CAP")
      (fields (field (name "PARTNO") "CC0402ZRY5V7BB104"))
      (libsource (lib "eagle-import") (part "CAP0402"))
    )
    (comp (ref "C613")
      (value "2u2")
      (footprint "eagle-import:0603-CAP")
      (fields (field (name "PARTNO") "C1608Y5V1C225Z"))
      (libsource (lib "eagle-import") (part "CAP0603"))
    )
    (comp (ref "C1001")
      (value "1u0")
      (footprint "eagle-import:0603-CAP")
      (fields (field (name "PARTNO") "CC0603ZRY5V7BB105"))
      (libsource (lib "eagle-import") (part "CAP0603"))
    )
    (comp (ref "C1002")
      (value "10n")
      (footprint "eagle-import:0402-CAP")
      (fields (field (name "PARTNO") "CC0402KRX7R7BB103"))
      (libsource (lib "eagle-import") (part "CAP0402"))
    )
    (comp (ref "C1003")
      (value "1u0")
      (footprint "eagle-import:0603-CAP")
      (fields (field (name "PARTNO") "CC0603ZRY5V7BB105"))
      (libsource (lib "eagle-import") (part "CAP0603"))
    )
    (comp (ref "C1004")
      (value "1u0")
      (footprint "eagle-import:0603-CAP")
      (fields (field (name "PARTNO") "CC0603ZRY5V7BB105"))
      (libsource (lib "eagle-import") (part "CAP0603"))
    )
    (comp (ref "JP3")
      (value "M01SMD-4.5X1.5")
      (footprint "eagle-import:PAD-1.5X4.5")
      (libsource (lib "eagle-import") (part "M01SMD-4.5X1.5"))
    )
    (comp (ref "R5")
      (value "10K")
      (footprint "eagle-import:0402-RES")
      (fields (field (name "PARTNO") "RC0402FR-0710KL"))
      (libsource (lib "eagle-import") (part "RESISTOR0402-RES"))
    )
    (comp (ref "R603")
      (value "10K")
      (footprint "eagle-import:0402-RES")
      (fields (field (name "PARTNO") "RC0402FR-0710KL"))
      (libsource (lib "eagle-import") (part "RESISTOR0402-RES"))
    )
    (comp (ref "R606")
      (value "25K")
      (footprint "eagle-import:0402-RES")
      (fields (field (name "PARTNO") "RMCF0402FT25K5"))
      (libsource (lib "eagle-import") (part "RESISTOR0402-RES"))
    )
    (comp (ref "R607")
      (value "10K")
      (footprint "eagle-import:0402-RES")
      (fields (field (name "PARTNO") "RC0402FR-0710KL"))
      (libsource (lib "eagle-import") (part "RESISTOR0402-RES"))
    )
    (comp (ref "R608")
      (value "1K")
      (footprint "eagle-import:0402-RES")
      (fields (field (name "PARTNO") "RC0402FR-071KL"))
      (libsource (lib "eagle-import") (part "RESISTOR0402-RES"))
    )
    (comp (ref "R609")
      (value "10K/0.1%")
      (footprint "eagle-import:0402-RES")
      (fields (field (name "PARTNO") "ERA-2AEB103X"))
      (libsource (lib "eagle-import") (part "RESISTOR0402-RES"))
    )
    (comp (ref "R610")
      (value "10K/0.1%")
      (footprint "eagle-import:0402-RES")
      (fields (field (name "PARTNO") "ERA-2AEB103X"))
      (libsource (lib "eagle-import") (part "RESISTOR0402-RES"))
    )
    (comp (ref "R611")
      (value "10K")
      (footprint "eagle-import:0402-RES")
      (fields (field (name "PARTNO") "RC0402FR-0710KL"))
      (libsource (lib "eagle-import") (part "RESISTOR0402-RES"))
    )
    (comp (ref "R1002")
      (value "10K")
      (footprint "eagle-import:0402-RES")
      (fields (field (name "PARTNO") "RC0402FR-0710KL"))
      (libsource (lib "eagle-import") (part "RESISTOR0402-RES"))
    )
    (comp (ref "S601")
      (value "RESET")
      (footprint "eagle-import:EVQP7J01K")
      (fields (field (name "PARTNO") "EVQP7J01K"))
      (libsource (lib "eagle-import") (part "SWITCH-MOMENTARY-2"))
    )
    (comp (ref "U$604")
      (value "BQ24315")
      (footprint "eagle-import:QFN8-DSG")
      (fields (field (name "PARTNO") "BQ24315DSGR"))
      (libsource (lib "eagle-import") (part "BQ24315"))
    )
    (comp (ref "U$605")
      (value "MIC5332")
      (footprint "eagle-import:MLF-8-EPAD")
      (fields (field (name "PARTNO") "MIC5332-SSYMT"))
      (libsource (lib "eagle-import") (part "MIC5332"))
    )
    (comp (ref "U$1002")
      (value "MIC5332")
      (footprint "eagle-import:MLF-8-EPAD")
      (fields (field (name "PARTNO") "MIC5332-SSYMT"))
      (libsource (lib "eagle-import") (part "MIC5332"))
    )
    (comp (ref "U101")
      (value "STM32F4X7VX")
      (footprint "eagle-import:TQFP100")
      (fields (field (name "PARTNO") "STM32F427VI"))
      (libsource (lib "eagle-import") (part "STM32F4X7VX"))
    )
    (comp (ref "J802")
      (value "DF13C-3P-1.25V")
      (footprint "eagle-import:DF13C-3P-1.25V")
      (fields (field (name "PARTNO") "DF13C-3P-1.25V(20)"))
      (libsource (lib "eagle-import") (part "DF13-3P-1.25V"))
    )
    (comp (ref "LED701")
      (value "AMBER")
      (footprint "eagle-import:0603-LED")
      (fields (field (name "PARTNO") "APTD1608SECK"))
      (libsource (lib "eagle-import") (part "LED0603"))
    )
    (comp (ref "LED704")
      (value "GREEN")
      (footprint "eagle-import:0603-LED")
      (fields (field (name "PARTNO") "APTD1608CGCK"))
      (libsource (lib "eagle-import") (part "LED0603"))
    )
    (comp (ref "R3")
      (value "220R")
      (footprint "eagle-import:0402-RES")
      (fields (field (name "PARTNO") "RC0402FR-07220RL"))
      (libsource (lib "eagle-import") (part "RESISTOR0402-RES"))
    )
    (comp (ref "R707")
      (value "220R")
      (footprint "eagle-import:0402-RES")
      (fields (field (name "PARTNO") "RC0402FR-07220RL"))
      (libsource (lib "eagle-import") (part "RESISTOR0402-RES"))
    )
    (comp (ref "R710")
      (value "47R")
      (footprint "eagle-import:0402-RES")
      (fields (field (name "PARTNO") "RC0402JR-0747RL"))
      (libsource (lib "eagle-import") (part "RESISTOR0402-RES"))
    )
    (comp (ref "R711")
      (value "220R")
      (footprint "eagle-import:0402-RES")
      (fields (field (name "PARTNO") "RC0402FR-07220RL"))
      (libsource (lib "eagle-import") (part "RESISTOR0402-RES"))
    )
    (comp (ref "R713")
      (value "1K5")
      (footprint "eagle-import:0402-RES")
      (fields (field (name "PARTNO") "RC0402FR-071K5L"))
      (libsource (lib "eagle-import") (part "RESISTOR0402-RES"))
    )
    (comp (ref "U$701")
      (value "PESD0402-140")
      (footprint "eagle-import:0402-TVS")
      (libsource (lib "eagle-import") (part "DIODE-TVS"))
    )
    (comp (ref "D1")
      (value "MSS1P4-M3")
      (footprint "eagle-import:MICROSMP")
      (fields (field (name "PARTNO") "MSS1P4-M3/89A"))
      (libsource (lib "eagle-import") (part "DIODE-SCHOTTKY_MSMP"))
    )
    (comp (ref "D2")
      (value "B340A")
      (footprint "eagle-import:SMA-DIODE")
      (libsource (lib "eagle-import") (part "DIODESMA"))
    )
    (comp (ref "D3")
      (value "DIODESOD")
      (footprint "eagle-import:SOD-323")
      (libsource (lib "eagle-import") (part "DIODESOD"))
    )
    (comp (ref "D5")
      (value "B340A")
      (footprint "eagle-import:SMA-DIODE")
      (libsource (lib "eagle-import") (part "DIODESMA"))
    )
    (comp (ref "JP5")
      (value "M02PTH3")
      (footprint "eagle-import:1X02_LONGPADS")
      (libsource (lib "eagle-import") (part "M02PTH3"))
    )
    (comp (ref "R918")
      (value "10K/0.1%")
      (footprint "eagle-import:0402-RES")
      (fields (field (name "PARTNO") "ERA-2AEB103X"))
      (libsource (lib "eagle-import") (part "RESISTOR0402-RES"))
    )
    (comp (ref "R919")
      (value "10K/0.1%")
      (footprint "eagle-import:0402-RES")
      (fields (field (name "PARTNO") "ERA-2AEB103X"))
      (libsource (lib "eagle-import") (part "RESISTOR0402-RES"))
    )
    (comp (ref "R922")
      (value "10K/0.1%")
      (footprint "eagle-import:0402-RES")
      (fields (field (name "PARTNO") "ERA-2AEB103X"))
      (libsource (lib "eagle-import") (part "RESISTOR0402-RES"))
    )
    (comp (ref "C102")
      (value "8p")
      (footprint "eagle-import:0402-CAP")
      (fields (field (name "PARTNO") "C1005C0G1H080C"))
      (libsource (lib "eagle-import") (part "CAP0402"))
    )
    (comp (ref "C103")
      (value "8p")
      (footprint "eagle-import:0402-CAP")
      (fields (field (name "PARTNO") "C1005C0G1H080C"))
      (libsource (lib "eagle-import") (part "CAP0402"))
    )
    (comp (ref "R102")
      (value "10K")
      (footprint "eagle-import:0402-RES")
      (fields (field (name "PARTNO") "RC0402FR-0710KL"))
      (libsource (lib "eagle-import") (part "RESISTOR0402-RES"))
    )
    (comp (ref "X101")
      (value "3.2x2.5 mm / 24 MHz / 15 ppm")
      (footprint "eagle-import:OSCILLATOR-3.2X2.5")
      (fields (field (name "PARTNO") "NX3225SA-24.000000MHZ"))
      (libsource (lib "eagle-import") (part "OSCILLATOR-3.2X2.5"))
    )
    (comp (ref "C2")
      (value "0u1")
      (footprint "eagle-import:0402-CAP")
      (fields (field (name "PARTNO") "CC0402ZRY5V7BB104"))
      (libsource (lib "eagle-import") (part "CAP0402"))
    )
    (comp (ref "C3")
      (value "0u1")
      (footprint "eagle-import:0402-CAP")
      (fields (field (name "PARTNO") "CC0402ZRY5V7BB104"))
      (libsource (lib "eagle-import") (part "CAP0402"))
    )
    (comp (ref "C4")
      (value "0u1")
      (footprint "eagle-import:0402-CAP")
      (fields (field (name "PARTNO") "CC0402ZRY5V7BB104"))
      (libsource (lib "eagle-import") (part "CAP0402"))
    )
    (comp (ref "C402")
      (value "0u1")
      (footprint "eagle-import:0402-CAP")
      (fields (field (name "PARTNO") "CC0402ZRY5V7BB104"))
      (libsource (lib "eagle-import") (part "CAP0402"))
    )
    (comp (ref "J2")
      (value "DF13-4P-1.25V")
      (footprint "eagle-import:DF13C-4P-1.25V")
      (fields (field (name "PARTNO") "DF13C-4P-1.25V(20)"))
      (libsource (lib "eagle-import") (part "DF13-4P-1.25V"))
    )
    (comp (ref "J3")
      (value "DF13C-4P-1.25V")
      (footprint "eagle-import:DF13C-4P-1.25V")
      (fields (field (name "PARTNO") "DF13C-4P-1.25V(20)"))
      (libsource (lib "eagle-import") (part "DF13-4P-1.25V"))
    )
    (comp (ref "J401")
      (value "DF13C-4P-1.25V")
      (footprint "eagle-import:DF13C-4P-1.25V")
      (fields (field (name "PARTNO") "DF13C-4P-1.25V(20)"))
      (libsource (lib "eagle-import") (part "DF13-4P-1.25V"))
    )
    (comp (ref "J403")
      (value "DF13C-7P-1.25V")
      (footprint "eagle-import:DF13C-7P-1.25V")
      (fields (field (name "PARTNO") "DF13C-7P-1.25V(20)"))
      (libsource (lib "eagle-import") (part "DF13-7P-1.25V"))
    )
    (comp (ref "J405")
      (value "DF13C-4P-1.25V")
      (footprint "eagle-import:DF13C-4P-1.25V")
      (fields (field (name "PARTNO") "DF13C-4P-1.25V(20)"))
      (libsource (lib "eagle-import") (part "DF13-4P-1.25V"))
    )
    (comp (ref "L4")
      (value "KNH16C104DA5TS")
      (footprint "eagle-import:KYOCERA-KNH16-DA")
      (libsource (lib "eagle-import") (part "KNH16C104DA5TS"))
    )
    (comp (ref "L5")
      (value "KNH16C104DA5TS")
      (footprint "eagle-import:KYOCERA-KNH16-DA")
      (libsource (lib "eagle-import") (part "KNH16C104DA5TS"))
    )
    (comp (ref "L6")
      (value "NUF8402MN")
      (footprint "eagle-import:DFN16-THIN")
      (libsource (lib "eagle-import") (part "NUF8402MN"))
    )
    (comp (ref "L7")
      (value "KNH16C104DA5TS")
      (footprint "eagle-import:KYOCERA-KNH16-DA")
      (libsource (lib "eagle-import") (part "KNH16C104DA5TS"))
    )
    (comp (ref "L402")
      (value "KNH16C104DA5TS")
      (footprint "eagle-import:KYOCERA-KNH16-DA")
      (libsource (lib "eagle-import") (part "KNH16C104DA5TS"))
    )
    (comp (ref "L403")
      (value "KNH16C104DA5TS")
      (footprint "eagle-import:KYOCERA-KNH16-DA")
      (libsource (lib "eagle-import") (part "KNH16C104DA5TS"))
    )
    (comp (ref "R1")
      (value "1K5")
      (footprint "eagle-import:0402-RES")
      (fields (field (name "PARTNO") "RC0402FR-071K5L"))
      (libsource (lib "eagle-import") (part "RESISTOR0402-RES"))
    )
    (comp (ref "R2")
      (value "1K5")
      (footprint "eagle-import:0402-RES")
      (fields (field (name "PARTNO") "RC0402FR-071K5L"))
      (libsource (lib "eagle-import") (part "RESISTOR0402-RES"))
    )
    (comp (ref "R4")
      (value "120R")
      (footprint "eagle-import:0402-RES")
      (fields (field (name "PARTNO") "RC0402FR-07120RL"))
      (libsource (lib "eagle-import") (part "RESISTOR0402-RES"))
    )
    (comp (ref "R401")
      (value "1K5")
      (footprint "eagle-import:0402-RES")
      (fields (field (name "PARTNO") "RC0402FR-071K5L"))
      (libsource (lib "eagle-import") (part "RESISTOR0402-RES"))
    )
    (comp (ref "R402")
      (value "1K5")
      (footprint "eagle-import:0402-RES")
      (fields (field (name "PARTNO") "RC0402FR-071K5L"))
      (libsource (lib "eagle-import") (part "RESISTOR0402-RES"))
    )
    (comp (ref "R407")
      (value "10K/0.1%")
      (footprint "eagle-import:0402-RES")
      (fields (field (name "PARTNO") "ERA-2AEB103X"))
      (libsource (lib "eagle-import") (part "RESISTOR0402-RES"))
    )
    (comp (ref "R408")
      (value "10K/0.1%")
      (footprint "eagle-import:0402-RES")
      (fields (field (name "PARTNO") "ERA-2AEB103X"))
      (libsource (lib "eagle-import") (part "RESISTOR0402-RES"))
    )
    (comp (ref "R409")
      (value "120R")
      (footprint "eagle-import:0402-RES")
      (fields (field (name "PARTNO") "RC0402FR-07120RL"))
      (libsource (lib "eagle-import") (part "RESISTOR0402-RES"))
    )
    (comp (ref "SJ1")
      (value "SOLDERJUMPERTRACE")
      (footprint "eagle-import:SJ_2S-TRACE")
      (libsource (lib "eagle-import") (part "SOLDERJUMPERTRACE"))
    )
    (comp (ref "SJ2")
      (value "SOLDERJUMPERTRACE")
      (footprint "eagle-import:SJ_2S-TRACE")
      (libsource (lib "eagle-import") (part "SOLDERJUMPERTRACE"))
    )
    (comp (ref "U$1")
      (value "HEADER-3X1BOARDEDGE-SHORT")
      (footprint "eagle-import:HEADER_3X01_SMD_H_BOARD_EDGE_SHORT")
      (libsource (lib "eagle-import") (part "HEADER-3X1BOARDEDGE-SHORT"))
    )
    (comp (ref "U$4")
      (value "PESD0402-140")
      (footprint "eagle-import:0402-TVS")
      (libsource (lib "eagle-import") (part "DIODE-TVS"))
    )
    (comp (ref "U$7")
      (value "PESD0402-140")
      (footprint "eagle-import:0402-TVS")
      (libsource (lib "eagle-import") (part "DIODE-TVS"))
    )
    (comp (ref "U$401")
      (value "PESD0402-140")
      (footprint "eagle-import:0402-TVS")
      (libsource (lib "eagle-import") (part "DIODE-TVS"))
    )
    (comp (ref "U$404")
      (value "PESD0402-140")
      (footprint "eagle-import:0402-TVS")
      (libsource (lib "eagle-import") (part "DIODE-TVS"))
    )
    (comp (ref "U2")
      (value "MAX3051")
      (footprint "eagle-import:SOT23-8")
      (fields (field (name "PARTNO") "MAX3051EKA"))
      (libsource (lib "eagle-import") (part "MAX3051MAX3051EKA"))
    )
    (comp (ref "U401")
      (value "MAX3051")
      (footprint "eagle-import:SOT23-8")
      (fields (field (name "PARTNO") "MAX3051EKA"))
      (libsource (lib "eagle-import") (part "MAX3051MAX3051EKA"))
    )
    (comp (ref "J1")
      (value "SERVO_HEADER-3X8")
      (footprint "eagle-import:3X8RA_SERVO")
      (libsource (lib "eagle-import") (part "SERVO_HEADER-3X8"))
    )
    (comp (ref "L1")
      (value "NUF8402MN")
      (footprint "eagle-import:DFN16-THIN")
      (libsource (lib "eagle-import") (part "NUF8402MN"))
    )
  )
  (nets
    (net (code "1") (name "ACCEL_DRDY") (class "Default")
      (node (ref "U$2") (pin "11") (pinfunction "INT1_11") (pintype "bidirectional"))
      (node (ref "U101") (pin "90") (pinfunction "PB4_90") (pintype "bidirectional"))
    )
    (net (code "2") (name "ALARM") (class "Default")
      (node (ref "U101") (pin "77") (pinfunction "PA15_77") (pintype "bidirectional"))
    )
    (net (code "3") (name "CAN1_H") (class "Default")
      (node (ref "J405") (pin "P$2") (pinfunction "2_P$2") (pintype "passive"))
      (node (ref "R409") (pin "P$1") (pinfunction "1_P$1") (pintype "passive"))
      (node (ref "U401") (pin "7") (pinfunction "CANH_7") (pintype "bidirectional"))
    )
    (net (code "4") (name "CAN1_L") (class "Default")
      (node (ref "J405") (pin "P$3") (pinfunction "3_P$3") (pintype "passive"))
      (node (ref "SJ1") (pin "2") (pinfunction "2_2") (pintype "passive"))
      (node (ref "U401") (pin "6") (pinfunction "CANL_6") (pintype "bidirectional"))
    )
    (net (code "5") (name "CAN1_RX") (class "Default")
      (node (ref "U101") (pin "81") (pinfunction "PD0_81") (pintype "bidirectional"))
      (node (ref "U401") (pin "4") (pinfunction "DOUT_4") (pintype "output"))
    )
    (net (code "6") (name "CAN1_TX") (class "Default")
      (node (ref "U101") (pin "82") (pinfunction "PD1_82") (pintype "bidirectional"))
      (node (ref "U401") (pin "1") (pinfunction "DIN_1") (pintype "input"))
    )
    (net (code "7") (name "CAN2_RX") (class "Default")
      (node (ref "U101") (pin "51") (pinfunction "PB12_51") (pintype "bidirectional"))
      (node (ref "U2") (pin "4") (pinfunction "DOUT_4") (pintype "output"))
    )
    (net (code "8") (name "CAN2_TX") (class "Default")
      (node (ref "U101") (pin "92") (pinfunction "PB6_92") (pintype "bidirectional"))
      (node (ref "U2") (pin "1") (pinfunction "DIN_1") (pintype "input"))
    )
    (net (code "9") (name "FMU-BOOT0") (class "Default")
      (node (ref "FMU-BOOT0") (pin "P$1") (pinfunction "P$1_P$1") (pintype "passive"))
      (node (ref "R611") (pin "P$2") (pinfunction "2_P$2") (pintype "passive"))
      (node (ref "U101") (pin "94") (pinfunction "BOOT0_94") (pintype "input"))
    )
    (net (code "10") (name "FMU-CH1") (class "Default")
      (node (ref "L1") (pin "P$1") (pinfunction "P$1_P$1") (pintype "bidirectional"))
      (node (ref "U101") (pin "45") (pinfunction "PE14_45") (pintype "bidirectional"))
    )
    (net (code "11") (name "FMU-CH2") (class "Default")
      (node (ref "L1") (pin "P$2") (pinfunction "P$1_P$2") (pintype "bidirectional"))
      (node (ref "U101") (pin "44") (pinfunction "PE13_44") (pintype "bidirectional"))
    )
    (net (code "12") (name "FMU-CH3") (class "Default")
      (node (ref "L1") (pin "P$3") (pinfunction "P$1_P$3") (pintype "bidirectional"))
      (node (ref "U101") (pin "42") (pinfunction "PE11_42") (pintype "bidirectional"))
    )
    (net (code "13") (name "FMU-CH4") (class "Default")
      (node (ref "L1") (pin "P$4") (pinfunction "P$1_P$4") (pintype "bidirectional"))
      (node (ref "U101") (pin "40") (pinfunction "PE9_40") (pintype "bidirectional"))
    )
    (net (code "14") (name "FMU-CH5") (class "Default")
      (node (ref "L1") (pin "P$5") (pinfunction "P$1_P$5") (pintype "bidirectional"))
      (node (ref "U101") (pin "60") (pinfunction "PD13_60") (pintype "bidirectional"))
    )
    (net (code "15") (name "FMU-CH6") (class "Default")
      (node (ref "L1") (pin "P$6") (pinfunction "P$1_P$6") (pintype "bidirectional"))
      (node (ref "U101") (pin "62") (pinfunction "PD15_62") (pintype "bidirectional"))
    )
    (net (code "16") (name "FMU-CH7") (class "Default")
      (node (ref "L1") (pin "P$7") (pinfunction "P$1_P$7") (pintype "bidirectional"))
      (node (ref "U101") (pin "24") (pinfunction "PA1_24") (pintype "bidirectional"))
    )
    (net (code "17") (name "FMU-CH8") (class "Default")
      (node (ref "L1") (pin "P$8") (pinfunction "P$1_P$8") (pintype "bidirectional"))
      (node (ref "U101") (pin "61") (pinfunction "PD14_61") (pintype "bidirectional"))
    )
    (net (code "18") (name "FMU-CH9") (class "Default")
      (node (ref "U101") (pin "25") (pinfunction "PA2_25") (pintype "bidirectional"))
    )
    (net (code "19") (name "FMU-CH10") (class "Default")
      (node (ref "U101") (pin "26") (pinfunction "PA3_26") (pintype "bidirectional"))
    )
    (net (code "20") (name "FMU-I2C1_SCL") (class "Default")
      (node (ref "L6") (pin "P$8") (pinfunction "P$1_P$8") (pintype "bidirectional"))
      (node (ref "R401") (pin "P$1") (pinfunction "1_P$1") (pintype "passive"))
      (node (ref "U101") (pin "95") (pinfunction "PB8_95") (pintype "bidirectional"))
    )
    (net (code "21") (name "FMU-I2C1_SDA") (class "Default")
      (node (ref "L6") (pin "P$7") (pinfunction "P$1_P$7") (pintype "bidirectional"))
      (node (ref "R402") (pin "P$1") (pinfunction "1_P$1") (pintype "passive"))
      (node (ref "U101") (pin "96") (pinfunction "PB9_96") (pintype "bidirectional"))
    )
    (net (code "22") (name "FMU-I2C2_SCL") (class "Default")
      (node (ref "L6") (pin "P$2") (pinfunction "P$1_P$2") (pintype "bidirectional"))
      (node (ref "R1") (pin "P$1") (pinfunction "1_P$1") (pintype "passive"))
      (node (ref "U101") (pin "47") (pinfunction "PB10_47") (pintype "bidirectional"))
    )
    (net (code "23") (name "FMU-I2C2_SDA") (class "Default")
      (node (ref "L6") (pin "P$1") (pinfunction "P$1_P$1") (pintype "bidirectional"))
      (node (ref "R2") (pin "P$1") (pinfunction "1_P$1") (pintype "passive"))
      (node (ref "U101") (pin "48") (pinfunction "PB11_48") (pintype "bidirectional"))
    )
    (net (code "24") (name "FMU-LED_SAFETY") (class "Default")
      (node (ref "R710") (pin "P$2") (pinfunction "2_P$2") (pintype "passive"))
    )
    (net (code "25") (name "FMU-SWCLK") (class "Default")
      (node (ref "JX301") (pin "4") (pinfunction "S_4") (pintype "passive"))
      (node (ref "U101") (pin "76") (pinfunction "PA14_76") (pintype "bidirectional"))
    )
    (net (code "26") (name "FMU-SWDIO") (class "Default")
      (node (ref "JX301") (pin "2") (pinfunction "S_2") (pintype "passive"))
      (node (ref "U101") (pin "72") (pinfunction "PA13_72") (pintype "bidirectional"))
    )
    (net (code "27") (name "FMU-SWO") (class "Default")
      (node (ref "JX301") (pin "6") (pinfunction "S_6") (pintype "passive"))
      (node (ref "U101") (pin "89") (pinfunction "PB3_89") (pintype "bidirectional"))
    )
    (net (code "28") (name "FMU-UART7_RX") (class "Default")
      (node (ref "L3") (pin "P$5") (pinfunction "P$1_P$5") (pintype "bidirectional"))
      (node (ref "U101") (pin "38") (pinfunction "PE7_38") (pintype "bidirectional"))
    )
    (net (code "29") (name "FMU-UART7_TX") (class "Default")
      (node (ref "L3") (pin "P$6") (pinfunction "P$1_P$6") (pintype "bidirectional"))
      (node (ref "U101") (pin "39") (pinfunction "PE8_39") (pintype "bidirectional"))
    )
    (net (code "30") (name "FMU-UART8_RX") (class "Default")
      (node (ref "U101") (pin "97") (pinfunction "PE0_97") (pintype "bidirectional"))
    )
    (net (code "31") (name "FMU-UART8_TX") (class "Default")
      (node (ref "U101") (pin "98") (pinfunction "PE1_98") (pintype "bidirectional"))
    )
    (net (code "32") (name "FMU-USART2_CTS") (class "Default")
      (node (ref "L2") (pin "P$8") (pinfunction "P$1_P$8") (pintype "bidirectional"))
      (node (ref "U101") (pin "84") (pinfunction "PD3_84") (pintype "bidirectional"))
    )
    (net (code "33") (name "FMU-USART2_RTS") (class "Default")
      (node (ref "L2") (pin "P$7") (pinfunction "P$1_P$7") (pintype "bidirectional"))
      (node (ref "U101") (pin "85") (pinfunction "PD4_85") (pintype "bidirectional"))
    )
    (net (code "34") (name "FMU-USART2_RX") (class "Default")
      (node (ref "L2") (pin "P$5") (pinfunction "P$1_P$5") (pintype "bidirectional"))
      (node (ref "U101") (pin "87") (pinfunction "PD6_87") (pintype "bidirectional"))
    )
    (net (code "35") (name "FMU-USART2_TX") (class "Default")
      (node (ref "L2") (pin "P$6") (pinfunction "P$1_P$6") (pintype "bidirectional"))
      (node (ref "U101") (pin "86") (pinfunction "PD5_86") (pintype "bidirectional"))
    )
    (net (code "36") (name "FMU-USART3_CTS") (class "Default")
      (node (ref "L2") (pin "P$2") (pinfunction "P$1_P$2") (pintype "bidirectional"))
      (node (ref "U101") (pin "58") (pinfunction "PD11_58") (pintype "bidirectional"))
    )
    (net (code "37") (name "FMU-USART3_RTS") (class "Default")
      (node (ref "L2") (pin "P$1") (pinfunction "P$1_P$1") (pintype "bidirectional"))
      (node (ref "U101") (pin "59") (pinfunction "PD12_59") (pintype "bidirectional"))
    )
    (net (code "38") (name "FMU-USART3_RX") (class "Default")
      (node (ref "L2") (pin "P$3") (pinfunction "P$1_P$3") (pintype "bidirectional"))
      (node (ref "U101") (pin "56") (pinfunction "PD9_56") (pintype "bidirectional"))
    )
    (net (code "39") (name "FMU-USART3_TX") (class "Default")
      (node (ref "L2") (pin "P$4") (pinfunction "P$1_P$4") (pintype "bidirectional"))
      (node (ref "U101") (pin "55") (pinfunction "PD8_55") (pintype "bidirectional"))
    )
    (net (code "40") (name "FMU-VDD_3V3") (class "Default")
      (node (ref "C13") (pin "P$1") (pinfunction "1_P$1") (pintype "passive"))
      (node (ref "C14") (pin "P$1") (pinfunction "1_P$1") (pintype "passive"))
      (node (ref "C15") (pin "P$1") (pinfunction "1_P$1") (pintype "passive"))
      (node (ref "C4") (pin "P$1") (pinfunction "1_P$1") (pintype "passive"))
      (node (ref "C402") (pin "P$1") (pinfunction "1_P$1") (pintype "passive"))
      (node (ref "C603") (pin "P$1") (pinfunction "1_P$1") (pintype "passive"))
      (node (ref "C604") (pin "P$1") (pinfunction "1_P$1") (pintype "passive"))
      (node (ref "C606") (pin "P$1") (pinfunction "1_P$1") (pintype "passive"))
      (node (ref "C607") (pin "P$1") (pinfunction "1_P$1") (pintype "passive"))
      (node (ref "C608") (pin "P$1") (pinfunction "1_P$1") (pintype "passive"))
      (node (ref "C610") (pin "P$1") (pinfunction "1_P$1") (pintype "passive"))
      (node (ref "C612") (pin "P$1") (pinfunction "1_P$1") (pintype "passive"))
      (node (ref "J802") (pin "P$1") (pinfunction "1_P$1") (pintype "passive"))
      (node (ref "JX301") (pin "1") (pinfunction "S_1") (pintype "passive"))
      (node (ref "R1") (pin "P$2") (pinfunction "2_P$2") (pintype "passive"))
      (node (ref "R2") (pin "P$2") (pinfunction "2_P$2") (pintype "passive"))
      (node (ref "R401") (pin "P$2") (pinfunction "2_P$2") (pintype "passive"))
      (node (ref "R402") (pin "P$2") (pinfunction "2_P$2") (pintype "passive"))
      (node (ref "R608") (pin "P$2") (pinfunction "2_P$2") (pintype "passive"))
      (node (ref "U$3") (pin "8") (pinfunction "VCC_8") (pintype "bidirectional"))
      (node (ref "U$605") (pin "7") (pinfunction "VOUT2_7") (pintype "bidirectional"))
      (node (ref "U$701") (pin "C") (pinfunction "C_C") (pintype "passive"))
      (node (ref "U101") (pin "100") (pinfunction "VDD_100") (pintype "power_in"))
      (node (ref "U101") (pin "11") (pinfunction "VDD_11") (pintype "power_in"))
      (node (ref "U101") (pin "19") (pinfunction "VDD_19") (pintype "power_in"))
      (node (ref "U101") (pin "21") (pinfunction "VREF+_21") (pintype "input"))
      (node (ref "U101") (pin "22") (pinfunction "VDDA_22") (pintype "power_in"))
      (node (ref "U101") (pin "28") (pinfunction "VDD_28") (pintype "power_in"))
      (node (ref "U101") (pin "50") (pinfunction "VDD_50") (pintype "power_in"))
      (node (ref "U101") (pin "75") (pinfunction "VDD_75") (pintype "power_in"))
      (node (ref "U2") (pin "3") (pinfunction "VCC_3") (pintype "input"))
      (node (ref "U401") (pin "3") (pinfunction "VCC_3") (pintype "input"))
    )
    (net (code "41") (name "FMU-~{RESET}") (class "Default")
      (node (ref "C609") (pin "P$2") (pinfunction "2_P$2") (pintype "passive"))
      (node (ref "S601") (pin "A1") (pinfunction "1_A1") (pintype "passive"))
      (node (ref "U$605") (pin "3") (pinfunction "POR2_3") (pintype "bidirectional"))
      (node (ref "U101") (pin "14") (pinfunction "NRST_14") (pintype "input"))
    )
    (net (code "42") (name "FMU_AUX_ADC1") (class "Default")
      (node (ref "R408") (pin "P$1") (pinfunction "1_P$1") (pintype "passive"))
      (node (ref "U101") (pin "18") (pinfunction "PC3_18") (pintype "bidirectional"))
    )
    (net (code "43") (name "FMU_AUX_ADC2") (class "Default")
      (node (ref "R407") (pin "P$1") (pinfunction "1_P$1") (pintype "passive"))
      (node (ref "U101") (pin "33") (pinfunction "PC4_33") (pintype "bidirectional"))
    )
    (net (code "44") (name "FRAM_MISO") (class "Default")
      (node (ref "U101") (pin "53") (pinfunction "PB14_53") (pintype "bidirectional"))
    )
    (net (code "45") (name "FRAM_MOSI") (class "Default")
      (node (ref "U101") (pin "54") (pinfunction "PB15_54") (pintype "bidirectional"))
    )
    (net (code "46") (name "FRAM_SCK") (class "Default")
      (node (ref "U101") (pin "52") (pinfunction "PB13_52") (pintype "bidirectional"))
    )
    (net (code "47") (name "GND") (class "Default")
      (node (ref "C1") (pin "2") (pinfunction "2_2") (pintype "passive"))
      (node (ref "C10") (pin "2") (pinfunction "2_2") (pintype "passive"))
      (node (ref "C1001") (pin "P$2") (pinfunction "2_P$2") (pintype "passive"))
      (node (ref "C1002") (pin "P$2") (pinfunction "2_P$2") (pintype "passive"))
      (node (ref "C1003") (pin "P$2") (pinfunction "2_P$2") (pintype "passive"))
      (node (ref "C1004") (pin "P$2") (pinfunction "2_P$2") (pintype "passive"))
      (node (ref "C102") (pin "P$2") (pinfunction "2_P$2") (pintype "passive"))
      (node (ref "C103") (pin "P$1") (pinfunction "1_P$1") (pintype "passive"))
      (node (ref "C12") (pin "P$2") (pinfunction "2_P$2") (pintype "passive"))
      (node (ref "C13") (pin "P$2") (pinfunction "2_P$2") (pintype "passive"))
      (node (ref "C14") (pin "P$2") (pinfunction "2_P$2") (pintype "passive"))
      (node (ref "C15") (pin "P$2") (pinfunction "2_P$2") (pintype "passive"))
      (node (ref "C2") (pin "P$2") (pinfunction "2_P$2") (pintype "passive"))
      (node (ref "C3") (pin "P$2") (pinfunction "2_P$2") (pintype "passive"))
      (node (ref "C4") (pin "P$2") (pinfunction "2_P$2") (pintype "passive"))
      (node (ref "C402") (pin "P$2") (pinfunction "2_P$2") (pintype "passive"))
      (node (ref "C5") (pin "P$2") (pinfunction "2_P$2") (pintype "passive"))
      (node (ref "C505") (pin "P$2") (pinfunction "2_P$2") (pintype "passive"))
      (node (ref "C506") (pin "P$2") (pinfunction "2_P$2") (pintype "passive"))
      (node (ref "C6") (pin "P$2") (pinfunction "2_P$2") (pintype "passive"))
      (node (ref "C601") (pin "P$2") (pinfunction "2_P$2") (pintype "passive"))
      (node (ref "C602") (pin "P$1") (pinfunction "1_P$1") (pintype "passive"))
      (node (ref "C603") (pin "P$2") (pinfunction "2_P$2") (pintype "passive"))
      (node (ref "C604") (pin "P$2") (pinfunction "2_P$2") (pintype "passive"))
      (node (ref "C605") (pin "P$2") (pinfunction "2_P$2") (pintype "passive"))
      (node (ref "C606") (pin "P$2") (pinfunction "2_P$2") (pintype "passive"))
      (node (ref "C607") (pin "P$2") (pinfunction "2_P$2") (pintype "passive"))
      (node (ref "C608") (pin "P$2") (pinfunction "2_P$2") (pintype "passive"))
      (node (ref "C609") (pin "P$1") (pinfunction "1_P$1") (pintype "passive"))
      (node (ref "C610") (pin "P$2") (pinfunction "2_P$2") (pintype "passive"))
      (node (ref "C611") (pin "P$2") (pinfunction "2_P$2") (pintype "passive"))
      (node (ref "C612") (pin "P$2") (pinfunction "2_P$2") (pintype "passive"))
      (node (ref "C613") (pin "P$2") (pinfunction "2_P$2") (pintype "passive"))
      (node (ref "C7") (pin "P$2") (pinfunction "2_P$2") (pintype "passive"))
      (node (ref "C8") (pin "2") (pinfunction "2_2") (pintype "passive"))
      (node (ref "C9") (pin "2") (pinfunction "2_2") (pintype "passive"))
      (node (ref "D3") (pin "2") (pinfunction "A_2") (pintype "passive"))
      (node (ref "J1") (pin "GND_S1") (pinfunction "S_GND_S1") (pintype "passive"))
      (node (ref "J1") (pin "GND_S2") (pinfunction "S_GND_S2") (pintype "passive"))
      (node (ref "J1") (pin "GND_S3") (pinfunction "S_GND_S3") (pintype "passive"))
      (node (ref "J1") (pin "GND_S4") (pinfunction "S_GND_S4") (pintype "passive"))
      (node (ref "J1") (pin "GND_S5") (pinfunction "S_GND_S5") (pintype "passive"))
      (node (ref "J1") (pin "GND_S6") (pinfunction "S_GND_S6") (pintype "passive"))
      (node (ref "J1") (pin "GND_S7") (pinfunction "S_GND_S7") (pintype "passive"))
      (node (ref "J1") (pin "GND_S8") (pinfunction "S_GND_S8") (pintype "passive"))
      (node (ref "J2") (pin "P$4") (pinfunction "4_P$4") (pintype "passive"))
      (node (ref "J201") (pin "P$6") (pinfunction "6_P$6") (pintype "passive"))
      (node (ref "J202") (pin "P$6") (pinfunction "6_P$6") (pintype "passive"))
      (node (ref "J203") (pin "P$6") (pinfunction "6_P$6") (pintype "passive"))
      (node (ref "J3") (pin "P$4") (pinfunction "4_P$4") (pintype "passive"))
      (node (ref "J302") (pin "P$4") (pinfunction "4_P$4") (pintype "passive"))
      (node (ref "J401") (pin "P$4") (pinfunction "4_P$4") (pintype "passive"))
      (node (ref "J403") (pin "P$7") (pinfunction "7_P$7") (pintype "passive"))
      (node (ref "J405") (pin "P$4") (pinfunction "4_P$4") (pintype "passive"))
      (node (ref "JP5") (pin "2") (pinfunction "2_2") (pintype "passive"))
      (node (ref "JX301") (pin "3") (pinfunction "S_3") (pintype "passive"))
      (node (ref "JX301") (pin "5") (pinfunction "S_5") (pintype "passive"))
      (node (ref "JX301") (pin "9") (pinfunction "S_9") (pintype "passive"))
      (node (ref "L1") (pin "P$EP") (pinfunction "GND_P$EP") (pintype "power_in"))
      (node (ref "L2") (pin "P$EP") (pinfunction "GND_P$EP") (pintype "power_in"))
      (node (ref "L201") (pin "P$3") (pinfunction "P$3_P$3") (pintype "bidirectional"))
      (node (ref "L201") (pin "P$4") (pinfunction "P$3_P$4") (pintype "bidirectional"))
      (node (ref "L201") (pin "P$5") (pinfunction "P$3_P$5") (pintype "bidirectional"))
      (node (ref "L202") (pin "P$3") (pinfunction "P$3_P$3") (pintype "bidirectional"))
      (node (ref "L202") (pin "P$4") (pinfunction "P$3_P$4") (pintype "bidirectional"))
      (node (ref "L202") (pin "P$5") (pinfunction "P$3_P$5") (pintype "bidirectional"))
      (node (ref "L203") (pin "P$3") (pinfunction "P$3_P$3") (pintype "bidirectional"))
      (node (ref "L203") (pin "P$4") (pinfunction "P$3_P$4") (pintype "bidirectional"))
      (node (ref "L203") (pin "P$5") (pinfunction "P$3_P$5") (pintype "bidirectional"))
      (node (ref "L3") (pin "P$EP") (pinfunction "GND_P$EP") (pintype "power_in"))
      (node (ref "L4") (pin "P$3") (pinfunction "P$3_P$3") (pintype "bidirectional"))
      (node (ref "L4") (pin "P$4") (pinfunction "P$3_P$4") (pintype "bidirectional"))
      (node (ref "L4") (pin "P$5") (pinfunction "P$3_P$5") (pintype "bidirectional"))
      (node (ref "L402") (pin "P$3") (pinfunction "P$3_P$3") (pintype "bidirectional"))
      (node (ref "L402") (pin "P$4") (pinfunction "P$3_P$4") (pintype "bidirectional"))
      (node (ref "L402") (pin "P$5") (pinfunction "P$3_P$5") (pintype "bidirectional"))
      (node (ref "L403") (pin "P$3") (pinfunction "P$3_P$3") (pintype "bidirectional"))
      (node (ref "L403") (pin "P$4") (pinfunction "P$3_P$4") (pintype "bidirectional"))
      (node (ref "L403") (pin "P$5") (pinfunction "P$3_P$5") (pintype "bidirectional"))
      (node (ref "L5") (pin "P$3") (pinfunction "P$3_P$3") (pintype "bidirectional"))
      (node (ref "L5") (pin "P$4") (pinfunction "P$3_P$4") (pintype "bidirectional"))
      (node (ref "L5") (pin "P$5") (pinfunction "P$3_P$5") (pintype "bidirectional"))
      (node (ref "L6") (pin "P$EP") (pinfunction "GND_P$EP") (pintype "power_in"))
      (node (ref "L7") (pin "P$3") (pinfunction "P$3_P$3") (pintype "bidirectional"))
      (node (ref "L7") (pin "P$4") (pinfunction "P$3_P$4") (pintype "bidirectional"))
      (node (ref "L7") (pin "P$5") (pinfunction "P$3_P$5") (pintype "bidirectional"))
      (node (ref "R1002") (pin "P$1") (pinfunction "1_P$1") (pintype "passive"))
      (node (ref "R102") (pin "P$2") (pinfunction "2_P$2") (pintype "passive"))
      (node (ref "R5") (pin "P$1") (pinfunction "1_P$1") (pintype "passive"))
      (node (ref "R603") (pin "P$1") (pinfunction "1_P$1") (pintype "passive"))
      (node (ref "R606") (pin "P$2") (pinfunction "2_P$2") (pintype "passive"))
      (node (ref "R610") (pin "P$2") (pinfunction "2_P$2") (pintype "passive"))
      (node (ref "R611") (pin "P$1") (pinfunction "1_P$1") (pintype "passive"))
      (node (ref "R711") (pin "P$1") (pinfunction "1_P$1") (pintype "passive"))
      (node (ref "R713") (pin "P$2") (pinfunction "2_P$2") (pintype "passive"))
      (node (ref "R919") (pin "P$1") (pinfunction "1_P$1") (pintype "passive"))
      (node (ref "S601") (pin "B3") (pinfunction "2_B3") (pintype "passive"))
      (node (ref "U$1") (pin "3") (pinfunction "3_3") (pintype "bidirectional"))
      (node (ref "U$1002") (pin "2") (pinfunction "GND_2") (pintype "bidirectional"))
      (node (ref "U$1002") (pin "GND") (pinfunction "GND_GND") (pintype "bidirectional"))
      (node (ref "U$14") (pin "3") (pinfunction "3_3") (pintype "bidirectional"))
      (node (ref "U$15") (pin "11") (pinfunction "GND_11") (pintype "power_in"))
      (node (ref "U$15") (pin "15") (pinfunction "PGND_15") (pintype "power_in"))
      (node (ref "U$15") (pin "16") (pinfunction "PGND_16") (pintype "power_in"))
      (node (ref "U$15") (pin "17") (pinfunction "PGND_17") (pintype "power_in"))
      (node (ref "U$15") (pin "18") (pinfunction "PGND_18") (pintype "power_in"))
      (node (ref "U$15") (pin "19") (pinfunction "PGND_19") (pintype "power_in"))
      (node (ref "U$15") (pin "20") (pinfunction "PGND_20") (pintype "power_in"))
      (node (ref "U$15") (pin "21") (pinfunction "PGND_21") (pintype "power_in"))
      (node (ref "U$15") (pin "22") (pinfunction "PGND_22") (pintype "power_in"))
      (node (ref "U$15") (pin "23") (pinfunction "PGND_23") (pintype "power_in"))
      (node (ref "U$15") (pin "4") (pinfunction "PS/SYNC_4") (pintype "input"))
      (node (ref "U$15") (pin "6") (pinfunction "PGND_6") (pintype "power_in"))
      (node (ref "U$15") (pin "7") (pinfunction "PGND_7") (pintype "power_in"))
      (node (ref "U$15") (pin "8") (pinfunction "PGND_8") (pintype "power_in"))
      (node (ref "U$15") (pin "9") (pinfunction "PGND_9") (pintype "power_in"))
      (node (ref "U$15") (pin "EP") (pinfunction "PGND_EP") (pintype "power_in"))
      (node (ref "U$2") (pin "10") (pinfunction "RSV1_10") (pintype "input"))
      (node (ref "U$2") (pin "5") (pinfunction "GND_5") (pintype "power_in"))
      (node (ref "U$201") (pin "A") (pinfunction "A_A") (pintype "passive"))
      (node (ref "U$202") (pin "A") (pinfunction "A_A") (pintype "passive"))
      (node (ref "U$203") (pin "A") (pinfunction "A_A") (pintype "passive"))
      (node (ref "U$3") (pin "4") (pinfunction "GND_4") (pintype "bidirectional"))
      (node (ref "U$4") (pin "A") (pinfunction "A_A") (pintype "passive"))
      (node (ref "U$401") (pin "A") (pinfunction "A_A") (pintype "passive"))
      (node (ref "U$404") (pin "A") (pinfunction "A_A") (pintype "passive"))
      (node (ref "U$5") (pin "2") (pinfunction "GND_2") (pintype "bidirectional"))
      (node (ref "U$604") (pin "2") (pinfunction "VSS_2") (pintype "bidirectional"))
      (node (ref "U$604") (pin "6") (pinfunction "VBAT_6") (pintype "bidirectional"))
      (node (ref "U$604") (pin "GND") (pinfunction "VSS_GND") (pintype "bidirectional"))
      (node (ref "U$604") (pin "P$2") (pinfunction "VSS_P$2") (pintype "bidirectional"))
      (node (ref "U$604") (pin "P$3") (pinfunction "VSS_P$3") (pintype "bidirectional"))
      (node (ref "U$605") (pin "2") (pinfunction "GND_2") (pintype "bidirectional"))
      (node (ref "U$605") (pin "GND") (pinfunction "GND_GND") (pintype "bidirectional"))
      (node (ref "U$7") (pin "A") (pinfunction "A_A") (pintype "passive"))
      (node (ref "U$701") (pin "A") (pinfunction "A_A") (pintype "passive"))
      (node (ref "U101") (pin "10") (pinfunction "VSS_10") (pintype "power_in"))
      (node (ref "U101") (pin "20") (pinfunction "VSSA_20") (pintype "power_in"))
      (node (ref "U101") (pin "27") (pinfunction "VSS_27") (pintype "power_in"))
      (node (ref "U101") (pin "74") (pinfunction "VSS_74") (pintype "power_in"))
      (node (ref "U101") (pin "99") (pinfunction "VSS_99") (pintype "power_in"))
      (node (ref "U2") (pin "2") (pinfunction "GND_2") (pintype "power_in"))
      (node (ref "U2") (pin "5") (pinfunction "SHDN_5") (pintype "input"))
      (node (ref "U2") (pin "8") (pinfunction "RS_8") (pintype "input"))
      (node (ref "U401") (pin "2") (pinfunction "GND_2") (pintype "power_in"))
      (node (ref "U401") (pin "5") (pinfunction "SHDN_5") (pintype "input"))
      (node (ref "U401") (pin "8") (pinfunction "RS_8") (pintype "input"))
      (node (ref "X101") (pin "2") (pinfunction "NC_2_2") (pintype "power_in"))
      (node (ref "X101") (pin "4") (pinfunction "NC_4_4") (pintype "power_in"))
    )
    (net (code "48") (name "GPIO_EXT_1") (class "Default")
      (node (ref "J403") (pin "P$6") (pinfunction "6_P$6") (pintype "passive"))
      (node (ref "U101") (pin "8") (pinfunction "PC14_8") (pintype "bidirectional"))
    )
    (net (code "49") (name "GYRO_DRDY") (class "Default")
      (node (ref "U$2") (pin "9") (pinfunction "INT2_9") (pintype "bidirectional"))
      (node (ref "U101") (pin "35") (pinfunction "PB0_35") (pintype "bidirectional"))
    )
    (net (code "50") (name "IO-~{RESET}") (class "Default")
      (node (ref "U$1002") (pin "3") (pinfunction "POR2_3") (pintype "bidirectional"))
    )
    (net (code "51") (name "MAG_DRDY") (class "Default")
      (node (ref "U101") (pin "36") (pinfunction "PB1_36") (pintype "bidirectional"))
    )
    (net (code "52") (name "Net-(C2-1)") (class "Default")
      (node (ref "C2") (pin "P$1") (pinfunction "1_P$1") (pintype "passive"))
      (node (ref "R408") (pin "P$2") (pinfunction "2_P$2") (pintype "passive"))
      (node (ref "U$1") (pin "2") (pinfunction "2_2") (pintype "bidirectional"))
    )
    (net (code "53") (name "Net-(C3-1)") (class "Default")
      (node (ref "C3") (pin "P$1") (pinfunction "1_P$1") (pintype "passive"))
      (node (ref "R407") (pin "P$2") (pinfunction "2_P$2") (pintype "passive"))
      (node (ref "U$1") (pin "1") (pinfunction "1_1") (pintype "bidirectional"))
    )
    (net (code "54") (name "Net-(C5-1)") (class "Default")
      (node (ref "C5") (pin "P$1") (pinfunction "1_P$1") (pintype "passive"))
      (node (ref "U$2") (pin "13") (pinfunction "REGD_13") (pintype "power_in"))
    )
    (net (code "55") (name "Net-(C6-1)") (class "Default")
      (node (ref "C6") (pin "P$1") (pinfunction "1_P$1") (pintype "passive"))
      (node (ref "U$15") (pin "10") (pinfunction "VAUX_10") (pintype "input"))
    )
    (net (code "56") (name "Net-(C102-1)") (class "Default")
      (node (ref "C102") (pin "P$1") (pinfunction "1_P$1") (pintype "passive"))
      (node (ref "U101") (pin "12") (pinfunction "OSC_IN_12") (pintype "input"))
      (node (ref "X101") (pin "3") (pinfunction "3_3") (pintype "bidirectional"))
    )
    (net (code "57") (name "Net-(C103-2)") (class "Default")
      (node (ref "C103") (pin "P$2") (pinfunction "2_P$2") (pintype "passive"))
      (node (ref "U101") (pin "13") (pinfunction "OSC_OUT_13") (pintype "output"))
      (node (ref "X101") (pin "1") (pinfunction "1_1") (pintype "bidirectional"))
    )
    (net (code "58") (name "Net-(C602-2)") (class "Default")
      (node (ref "C602") (pin "P$2") (pinfunction "2_P$2") (pintype "passive"))
      (node (ref "U$605") (pin "6") (pinfunction "CSET_6") (pintype "bidirectional"))
    )
    (net (code "59") (name "Net-(C611-1)") (class "Default")
      (node (ref "C611") (pin "P$1") (pinfunction "1_P$1") (pintype "passive"))
      (node (ref "U101") (pin "49") (pinfunction "VCAP_1_49") (pintype "power_in"))
    )
    (net (code "60") (name "Net-(C613-1)") (class "Default")
      (node (ref "C613") (pin "P$1") (pinfunction "1_P$1") (pintype "passive"))
      (node (ref "U101") (pin "73") (pinfunction "VCAP_2_73") (pintype "power_in"))
    )
    (net (code "61") (name "Net-(C1002-1)") (class "Default")
      (node (ref "C1002") (pin "P$1") (pinfunction "1_P$1") (pintype "passive"))
      (node (ref "U$1002") (pin "6") (pinfunction "CSET_6") (pintype "bidirectional"))
    )
    (net (code "62") (name "Net-(D3-C)") (class "Default")
      (node (ref "D3") (pin "1") (pinfunction "C_1") (pintype "passive"))
      (node (ref "R918") (pin "P$2") (pinfunction "2_P$2") (pintype "passive"))
      (node (ref "R922") (pin "P$1") (pinfunction "1_P$1") (pintype "passive"))
    )
    (net (code "63") (name "Net-(J1A-S)") (class "Default")
      (node (ref "J1") (pin "S1") (pinfunction "S_S1") (pintype "passive"))
      (node (ref "L1") (pin "P$16") (pinfunction "P$2_P$16") (pintype "bidirectional"))
    )
    (net (code "64") (name "Net-(J1B-S)") (class "Default")
      (node (ref "J1") (pin "S2") (pinfunction "S_S2") (pintype "passive"))
      (node (ref "L1") (pin "P$15") (pinfunction "P$2_P$15") (pintype "bidirectional"))
    )
    (net (code "65") (name "Net-(J1C-S)") (class "Default")
      (node (ref "J1") (pin "S3") (pinfunction "S_S3") (pintype "passive"))
      (node (ref "L1") (pin "P$14") (pinfunction "P$2_P$14") (pintype "bidirectional"))
    )
    (net (code "66") (name "Net-(J1D-S)") (class "Default")
      (node (ref "J1") (pin "S4") (pinfunction "S_S4") (pintype "passive"))
      (node (ref "L1") (pin "P$13") (pinfunction "P$2_P$13") (pintype "bidirectional"))
    )
    (net (code "67") (name "Net-(J1E-S)") (class "Default")
      (node (ref "J1") (pin "S5") (pinfunction "S_S5") (pintype "passive"))
      (node (ref "L1") (pin "P$12") (pinfunction "P$2_P$12") (pintype "bidirectional"))
    )
    (net (code "68") (name "Net-(J1F-S)") (class "Default")
      (node (ref "J1") (pin "S6") (pinfunction "S_S6") (pintype "passive"))
      (node (ref "L1") (pin "P$11") (pinfunction "P$2_P$11") (pintype "bidirectional"))
    )
    (net (code "69") (name "Net-(J1G-S)") (class "Default")
      (node (ref "J1") (pin "S7") (pinfunction "S_S7") (pintype "passive"))
      (node (ref "L1") (pin "P$10") (pinfunction "P$2_P$10") (pintype "bidirectional"))
    )
    (net (code "70") (name "Net-(J1H-S)") (class "Default")
      (node (ref "J1") (pin "S8") (pinfunction "S_S8") (pintype "passive"))
      (node (ref "L1") (pin "P$9") (pinfunction "P$2_P$9") (pintype "bidirectional"))
    )
    (net (code "71") (name "Net-(J2-1)") (class "Default")
      (node (ref "J2") (pin "P$1") (pinfunction "1_P$1") (pintype "passive"))
      (node (ref "L5") (pin "P$2") (pinfunction "P$2_P$2") (pintype "bidirectional"))
      (node (ref "U$4") (pin "C") (pinfunction "C_C") (pintype "passive"))
    )
    (net (code "72") (name "Net-(J2-2)") (class "Default")
      (node (ref "J2") (pin "P$2") (pinfunction "2_P$2") (pintype "passive"))
      (node (ref "L6") (pin "P$15") (pinfunction "P$2_P$15") (pintype "bidirectional"))
    )
    (net (code "73") (name "Net-(J2-3)") (class "Default")
      (node (ref "J2") (pin "P$3") (pinfunction "3_P$3") (pintype "passive"))
      (node (ref "L6") (pin "P$16") (pinfunction "P$2_P$16") (pintype "bidirectional"))
    )
    (net (code "74") (name "Net-(J3-1)") (class "Default")
      (node (ref "J3") (pin "P$1") (pinfunction "1_P$1") (pintype "passive"))
      (node (ref "L7") (pin "P$2") (pinfunction "P$2_P$2") (pintype "bidirectional"))
      (node (ref "U$7") (pin "C") (pinfunction "C_C") (pintype "passive"))
    )
    (net (code "75") (name "Net-(J3-2)") (class "Default")
      (node (ref "J3") (pin "P$2") (pinfunction "2_P$2") (pintype "passive"))
      (node (ref "R4") (pin "P$1") (pinfunction "1_P$1") (pintype "passive"))
      (node (ref "U2") (pin "7") (pinfunction "CANH_7") (pintype "bidirectional"))
    )
    (net (code "76") (name "Net-(J3-3)") (class "Default")
      (node (ref "J3") (pin "P$3") (pinfunction "3_P$3") (pintype "passive"))
      (node (ref "SJ2") (pin "2") (pinfunction "2_2") (pintype "passive"))
      (node (ref "U2") (pin "6") (pinfunction "CANL_6") (pintype "bidirectional"))
    )
    (net (code "77") (name "Net-(J201-1)") (class "Default")
      (node (ref "J201") (pin "P$1") (pinfunction "1_P$1") (pintype "passive"))
      (node (ref "L201") (pin "P$2") (pinfunction "P$2_P$2") (pintype "bidirectional"))
      (node (ref "U$201") (pin "C") (pinfunction "C_C") (pintype "passive"))
    )
    (net (code "78") (name "Net-(J202-1)") (class "Default")
      (node (ref "J202") (pin "P$1") (pinfunction "1_P$1") (pintype "passive"))
      (node (ref "L202") (pin "P$2") (pinfunction "P$2_P$2") (pintype "bidirectional"))
      (node (ref "U$202") (pin "C") (pinfunction "C_C") (pintype "passive"))
    )
    (net (code "79") (name "Net-(J203-1)") (class "Default")
      (node (ref "J203") (pin "P$1") (pinfunction "1_P$1") (pintype "passive"))
      (node (ref "L203") (pin "P$2") (pinfunction "P$2_P$2") (pintype "bidirectional"))
      (node (ref "U$203") (pin "C") (pinfunction "C_C") (pintype "passive"))
    )
    (net (code "80") (name "Net-(J302-2)") (class "Default")
      (node (ref "J302") (pin "P$2") (pinfunction "2_P$2") (pintype "passive"))
      (node (ref "U$5") (pin "1") (pinfunction "D1I_1") (pintype "bidirectional"))
    )
    (net (code "81") (name "Net-(J302-3)") (class "Default")
      (node (ref "J302") (pin "P$3") (pinfunction "3_P$3") (pintype "passive"))
      (node (ref "U$5") (pin "3") (pinfunction "D2I_3") (pintype "bidirectional"))
    )
    (net (code "82") (name "Net-(J401-1)") (class "Default")
      (node (ref "J401") (pin "P$1") (pinfunction "1_P$1") (pintype "passive"))
      (node (ref "L4") (pin "P$2") (pinfunction "P$2_P$2") (pintype "bidirectional"))
      (node (ref "U$401") (pin "C") (pinfunction "C_C") (pintype "passive"))
    )
    (net (code "83") (name "Net-(J401-2)") (class "Default")
      (node (ref "J401") (pin "P$2") (pinfunction "2_P$2") (pintype "passive"))
      (node (ref "L6") (pin "P$9") (pinfunction "P$2_P$9") (pintype "bidirectional"))
    )
    (net (code "84") (name "Net-(J401-3)") (class "Default")
      (node (ref "J401") (pin "P$3") (pinfunction "3_P$3") (pintype "passive"))
      (node (ref "L6") (pin "P$10") (pinfunction "P$2_P$10") (pintype "bidirectional"))
    )
    (net (code "85") (name "Net-(J403-1)") (class "Default")
      (node (ref "J403") (pin "P$1") (pinfunction "1_P$1") (pintype "passive"))
      (node (ref "L402") (pin "P$2") (pinfunction "P$2_P$2") (pintype "bidirectional"))
    )
    (net (code "86") (name "Net-(J405-1)") (class "Default")
      (node (ref "J405") (pin "P$1") (pinfunction "1_P$1") (pintype "passive"))
      (node (ref "L403") (pin "P$2") (pinfunction "P$2_P$2") (pintype "bidirectional"))
      (node (ref "U$404") (pin "C") (pinfunction "C_C") (pintype "passive"))
    )
    (net (code "87") (name "Net-(J802-2)") (class "Default")
      (node (ref "J802") (pin "P$2") (pinfunction "2_P$2") (pintype "passive"))
      (node (ref "R710") (pin "P$1") (pinfunction "1_P$1") (pintype "passive"))
    )
    (net (code "88") (name "Net-(L3C-P$2)") (class "Default")
      (node (ref "L3") (pin "P$13") (pinfunction "P$2_P$13") (pintype "bidirectional"))
      (node (ref "L3") (pin "P$14") (pinfunction "P$2_P$14") (pintype "bidirectional"))
      (node (ref "U$14") (pin "1") (pinfunction "1_1") (pintype "bidirectional"))
    )
    (net (code "89") (name "Net-(R3-1)") (class "Default")
      (node (ref "R3") (pin "P$1") (pinfunction "1_P$1") (pintype "passive"))
      (node (ref "R707") (pin "P$2") (pinfunction "2_P$2") (pintype "passive"))
    )
    (net (code "90") (name "Net-(R3-2)") (class "Default")
      (node (ref "LED701") (pin "C") (pinfunction "C_C") (pintype "passive"))
      (node (ref "R3") (pin "P$2") (pinfunction "2_P$2") (pintype "passive"))
    )
    (net (code "91") (name "Net-(R4-2)") (class "Default")
      (node (ref "R4") (pin "P$2") (pinfunction "2_P$2") (pintype "passive"))
      (node (ref "SJ2") (pin "1") (pinfunction "1_1") (pintype "passive"))
    )
    (net (code "92") (name "Net-(R102-1)") (class "Default")
      (node (ref "R102") (pin "P$1") (pinfunction "1_P$1") (pintype "passive"))
      (node (ref "U101") (pin "37") (pinfunction "PB2_37") (pintype "bidirectional"))
    )
    (net (code "93") (name "Net-(R409-2)") (class "Default")
      (node (ref "R409") (pin "P$2") (pinfunction "2_P$2") (pintype "passive"))
      (node (ref "SJ1") (pin "1") (pinfunction "1_1") (pintype "passive"))
    )
    (net (code "94") (name "Net-(R606-1)") (class "Default")
      (node (ref "R606") (pin "P$1") (pinfunction "1_P$1") (pintype "passive"))
      (node (ref "U$604") (pin "7") (pinfunction "ILIM_7") (pintype "bidirectional"))
    )
    (net (code "95") (name "Net-(R711-2)") (class "Default")
      (node (ref "LED704") (pin "C") (pinfunction "C_C") (pintype "passive"))
      (node (ref "R711") (pin "P$2") (pinfunction "2_P$2") (pintype "passive"))
    )
    (net (code "96") (name "Net-(U$15-L1)") (class "Default")
      (node (ref "U$15") (pin "1") (pinfunction "L1_1") (pintype "bidirectional"))
      (node (ref "U$16") (pin "2") (pinfunction "2_2") (pintype "passive"))
    )
    (net (code "97") (name "Net-(U$15-L2)") (class "Default")
      (node (ref "U$15") (pin "14") (pinfunction "L2_14") (pintype "bidirectional"))
      (node (ref "U$16") (pin "1") (pinfunction "1_1") (pintype "passive"))
    )
    (net (code "98") (name "OTG_FS_DM") (class "Default")
      (node (ref "U$5") (pin "4") (pinfunction "D2O_4") (pintype "bidirectional"))
      (node (ref "U101") (pin "70") (pinfunction "PA11_70") (pintype "bidirectional"))
    )
    (net (code "99") (name "OTG_FS_DP") (class "Default")
      (node (ref "U$5") (pin "6") (pinfunction "D1O_6") (pintype "bidirectional"))
      (node (ref "U101") (pin "71") (pinfunction "PA12_71") (pintype "bidirectional"))
    )
    (net (code "100") (name "PPM_INPUT") (class "Default")
      (node (ref "L3") (pin "P$3") (pinfunction "P$1_P$3") (pintype "bidirectional"))
      (node (ref "U101") (pin "23") (pinfunction "PA0_23") (pintype "bidirectional"))
    )
    (net (code "101") (name "SAFETY") (class "Default")
      (node (ref "J802") (pin "P$3") (pinfunction "3_P$3") (pintype "passive"))
      (node (ref "R713") (pin "P$1") (pinfunction "1_P$1") (pintype "passive"))
    )
    (net (code "102") (name "SDIO_CK") (class "Default")
      (node (ref "U$3") (pin "6") (pinfunction "CLK_6") (pintype "bidirectional"))
      (node (ref "U101") (pin "80") (pinfunction "PC12_80") (pintype "bidirectional"))
    )
    (net (code "103") (name "SDIO_CMD") (class "Default")
      (node (ref "U$3") (pin "1") (pinfunction "~{CS}_1") (pintype "bidirectional"))
      (node (ref "U101") (pin "83") (pinfunction "PD2_83") (pintype "bidirectional"))
    )
    (net (code "104") (name "SDIO_D0") (class "Default")
      (node (ref "U$3") (pin "5") (pinfunction "DI/IO0_5") (pintype "bidirectional"))
      (node (ref "U101") (pin "65") (pinfunction "PC8_65") (pintype "bidirectional"))
    )
    (net (code "105") (name "SDIO_D1") (class "Default")
      (node (ref "U$3") (pin "2") (pinfunction "DO/IO1_2") (pintype "bidirectional"))
      (node (ref "U101") (pin "66") (pinfunction "PC9_66") (pintype "bidirectional"))
    )
    (net (code "106") (name "SDIO_D2") (class "Default")
      (node (ref "U$3") (pin "3") (pinfunction "~{WP}/IO2_3") (pintype "bidirectional"))
      (node (ref "U101") (pin "78") (pinfunction "PC10_78") (pintype "bidirectional"))
    )
    (net (code "107") (name "SDIO_D3") (class "Default")
      (node (ref "U$3") (pin "7") (pinfunction "~{HOLD}/IO3_7") (pintype "bidirectional"))
      (node (ref "U101") (pin "79") (pinfunction "PC11_79") (pintype "bidirectional"))
    )
    (net (code "108") (name "SERIAL1_CTS") (class "Default")
      (node (ref "J201") (pin "P$4") (pinfunction "4_P$4") (pintype "passive"))
      (node (ref "L2") (pin "P$9") (pinfunction "P$2_P$9") (pintype "bidirectional"))
    )
    (net (code "109") (name "SERIAL1_RTS") (class "Default")
      (node (ref "J201") (pin "P$5") (pinfunction "5_P$5") (pintype "passive"))
      (node (ref "L2") (pin "P$10") (pinfunction "P$2_P$10") (pintype "bidirectional"))
    )
    (net (code "110") (name "SERIAL1_RX") (class "Default")
      (node (ref "J201") (pin "P$3") (pinfunction "3_P$3") (pintype "passive"))
      (node (ref "L2") (pin "P$12") (pinfunction "P$2_P$12") (pintype "bidirectional"))
    )
    (net (code "111") (name "SERIAL1_TX") (class "Default")
      (node (ref "J201") (pin "P$2") (pinfunction "2_P$2") (pintype "passive"))
      (node (ref "L2") (pin "P$11") (pinfunction "P$2_P$11") (pintype "bidirectional"))
    )
    (net (code "112") (name "SERIAL2_CTS") (class "Default")
      (node (ref "J202") (pin "P$4") (pinfunction "4_P$4") (pintype "passive"))
      (node (ref "L2") (pin "P$15") (pinfunction "P$2_P$15") (pintype "bidirectional"))
    )
    (net (code "113") (name "SERIAL2_RTS") (class "Default")
      (node (ref "J202") (pin "P$5") (pinfunction "5_P$5") (pintype "passive"))
      (node (ref "L2") (pin "P$16") (pinfunction "P$2_P$16") (pintype "bidirectional"))
    )
    (net (code "114") (name "SERIAL2_RX") (class "Default")
      (node (ref "J202") (pin "P$3") (pinfunction "3_P$3") (pintype "passive"))
      (node (ref "L2") (pin "P$14") (pinfunction "P$2_P$14") (pintype "bidirectional"))
    )
    (net (code "115") (name "SERIAL2_TX") (class "Default")
      (node (ref "J202") (pin "P$2") (pinfunction "2_P$2") (pintype "passive"))
      (node (ref "L2") (pin "P$13") (pinfunction "P$2_P$13") (pintype "bidirectional"))
    )
    (net (code "116") (name "SERIAL3_RX") (class "Default")
      (node (ref "J203") (pin "P$3") (pinfunction "3_P$3") (pintype "passive"))
      (node (ref "L3") (pin "P$12") (pinfunction "P$2_P$12") (pintype "bidirectional"))
    )
    (net (code "117") (name "SERIAL3_TX") (class "Default")
      (node (ref "J203") (pin "P$2") (pinfunction "2_P$2") (pintype "passive"))
      (node (ref "L3") (pin "P$11") (pinfunction "P$2_P$11") (pintype "bidirectional"))
    )
    (net (code "118") (name "SPEKTRUM_RX") (class "Default")
      (node (ref "L3") (pin "P$4") (pinfunction "P$1_P$4") (pintype "bidirectional"))
      (node (ref "U101") (pin "69") (pinfunction "PA10_69") (pintype "bidirectional"))
    )
    (net (code "119") (name "SPI_EXT_MISO") (class "Default")
      (node (ref "J403") (pin "P$3") (pinfunction "3_P$3") (pintype "passive"))
      (node (ref "U101") (pin "4") (pinfunction "PE5_4") (pintype "bidirectional"))
    )
    (net (code "120") (name "SPI_EXT_MOSI") (class "Default")
      (node (ref "J403") (pin "P$4") (pinfunction "4_P$4") (pintype "passive"))
      (node (ref "U101") (pin "5") (pinfunction "PE6_5") (pintype "bidirectional"))
    )
    (net (code "121") (name "SPI_EXT_SCK") (class "Default")
      (node (ref "J403") (pin "P$2") (pinfunction "2_P$2") (pintype "passive"))
      (node (ref "U101") (pin "1") (pinfunction "PE2_1") (pintype "bidirectional"))
    )
    (net (code "122") (name "SPI_INT_MISO") (class "Default")
      (node (ref "U$2") (pin "7") (pinfunction "SA0/MISO_7") (pintype "bidirectional"))
      (node (ref "U101") (pin "31") (pinfunction "PA6_31") (pintype "bidirectional"))
    )
    (net (code "123") (name "SPI_INT_MOSI") (class "Default")
      (node (ref "U$2") (pin "6") (pinfunction "SDA/MOSI_6") (pintype "bidirectional"))
      (node (ref "U101") (pin "32") (pinfunction "PA7_32") (pintype "bidirectional"))
    )
    (net (code "124") (name "SPI_INT_SCK") (class "Default")
      (node (ref "U$2") (pin "4") (pinfunction "SCL/CLK_4") (pintype "bidirectional"))
      (node (ref "U101") (pin "30") (pinfunction "PA5_30") (pintype "bidirectional"))
    )
    (net (code "125") (name "VBAT") (class "Default")
      (node (ref "JP3") (pin "P$1") (pinfunction "1_P$1") (pintype "passive"))
      (node (ref "R608") (pin "P$1") (pinfunction "1_P$1") (pintype "passive"))
      (node (ref "U101") (pin "6") (pinfunction "VBAT_6") (pintype "power_in"))
    )
    (net (code "126") (name "VBUS") (class "Default")
      (node (ref "D1") (pin "ANODE") (pinfunction "A_ANODE") (pintype "passive"))
      (node (ref "J302") (pin "P$1") (pinfunction "1_P$1") (pintype "passive"))
      (node (ref "U$5") (pin "5") (pinfunction "VBUS_5") (pintype "bidirectional"))
      (node (ref "U101") (pin "68") (pinfunction "PA9_68") (pintype "bidirectional"))
    )
    (net (code "127") (name "VDD_3V3_PERIPH") (class "Default")
      (node (ref "C1004") (pin "P$1") (pinfunction "1_P$1") (pintype "passive"))
      (node (ref "U$1002") (pin "7") (pinfunction "VOUT2_7") (pintype "bidirectional"))
    )
    (net (code "128") (name "VDD_3V3_PERIPH_EN") (class "Default")
      (node (ref "R5") (pin "P$2") (pinfunction "2_P$2") (pintype "passive"))
      (node (ref "U$1002") (pin "4") (pinfunction "EN2_4") (pintype "bidirectional"))
    )
    (net (code "129") (name "VDD_3V3_SENSORS") (class "Default")
      (node (ref "C1003") (pin "P$1") (pinfunction "1_P$1") (pintype "passive"))
      (node (ref "C505") (pin "P$1") (pinfunction "1_P$1") (pintype "passive"))
      (node (ref "C506") (pin "P$1") (pinfunction "1_P$1") (pintype "passive"))
      (node (ref "U$1002") (pin "8") (pinfunction "VOUT1_8") (pintype "bidirectional"))
      (node (ref "U$2") (pin "1") (pinfunction "VDD_IO_1") (pintype "power_in"))
      (node (ref "U$2") (pin "14") (pinfunction "VDD_14") (pintype "power_in"))
      (node (ref "U$2") (pin "15") (pinfunction "RSV2_15") (pintype "input"))
    )
    (net (code "130") (name "VDD_3V3_SENSORS_EN") (class "Default")
      (node (ref "R1002") (pin "P$2") (pinfunction "2_P$2") (pintype "passive"))
      (node (ref "U$1002") (pin "5") (pinfunction "EN1_5") (pintype "bidirectional"))
      (node (ref "U101") (pin "2") (pinfunction "PE3_2") (pintype "bidirectional"))
    )
    (net (code "131") (name "VDD_3V3_SPEKTRUM") (class "Default")
      (node (ref "C605") (pin "P$1") (pinfunction "1_P$1") (pintype "passive"))
      (node (ref "U$14") (pin "2") (pinfunction "2_2") (pintype "bidirectional"))
      (node (ref "U$605") (pin "8") (pinfunction "VOUT1_8") (pintype "bidirectional"))
    )
    (net (code "132") (name "VDD_3V3_SPEKTRUM_EN") (class "Default")
      (node (ref "R603") (pin "P$2") (pinfunction "2_P$2") (pintype "passive"))
      (node (ref "U$605") (pin "5") (pinfunction "EN1_5") (pintype "bidirectional"))
    )
    (net (code "133") (name "VDD_5V") (class "Default")
      (node (ref "C10") (pin "1") (pinfunction "1_1") (pintype "passive"))
      (node (ref "C1001") (pin "P$1") (pinfunction "1_P$1") (pintype "passive"))
      (node (ref "C601") (pin "P$1") (pinfunction "1_P$1") (pintype "passive"))
      (node (ref "C7") (pin "P$1") (pinfunction "1_P$1") (pintype "passive"))
      (node (ref "C8") (pin "1") (pinfunction "1_1") (pintype "passive"))
      (node (ref "C9") (pin "1") (pinfunction "1_1") (pintype "passive"))
      (node (ref "LED701") (pin "A") (pinfunction "A_A") (pintype "passive"))
      (node (ref "LED704") (pin "A") (pinfunction "A_A") (pintype "passive"))
      (node (ref "R607") (pin "P$1") (pinfunction "1_P$1") (pintype "passive"))
      (node (ref "R609") (pin "P$2") (pinfunction "2_P$2") (pintype "passive"))
      (node (ref "U$1002") (pin "1") (pinfunction "VIN_1") (pintype "bidirectional"))
      (node (ref "U$15") (pin "13") (pinfunction "VOUT_13") (pintype "power_in"))
      (node (ref "U$604") (pin "1") (pinfunction "IN_1") (pintype "bidirectional"))
      (node (ref "U$605") (pin "1") (pinfunction "VIN_1") (pintype "bidirectional"))
      (node (ref "U$605") (pin "4") (pinfunction "EN2_4") (pintype "bidirectional"))
    )
    (net (code "134") (name "VDD_5V_PERIPH") (class "Default")
      (node (ref "L201") (pin "P$1") (pinfunction "P$1_P$1") (pintype "bidirectional"))
      (node (ref "L202") (pin "P$1") (pinfunction "P$1_P$1") (pintype "bidirectional"))
      (node (ref "L203") (pin "P$1") (pinfunction "P$1_P$1") (pintype "bidirectional"))
      (node (ref "L4") (pin "P$1") (pinfunction "P$1_P$1") (pintype "bidirectional"))
      (node (ref "L402") (pin "P$1") (pinfunction "P$1_P$1") (pintype "bidirectional"))
      (node (ref "L403") (pin "P$1") (pinfunction "P$1_P$1") (pintype "bidirectional"))
      (node (ref "L5") (pin "P$1") (pinfunction "P$1_P$1") (pintype "bidirectional"))
      (node (ref "L7") (pin "P$1") (pinfunction "P$1_P$1") (pintype "bidirectional"))
      (node (ref "U$604") (pin "8") (pinfunction "OUT_8") (pintype "bidirectional"))
    )
    (net (code "135") (name "VDD_5V_SENS") (class "Default")
      (node (ref "R609") (pin "P$1") (pinfunction "1_P$1") (pintype "passive"))
      (node (ref "R610") (pin "P$1") (pinfunction "1_P$1") (pintype "passive"))
      (node (ref "U101") (pin "29") (pinfunction "PA4_29") (pintype "bidirectional"))
    )
    (net (code "136") (name "VDD_IN") (class "Default")
      (node (ref "C1") (pin "1") (pinfunction "1_1") (pintype "passive"))
      (node (ref "C12") (pin "P$1") (pinfunction "1_P$1") (pintype "passive"))
      (node (ref "D1") (pin "CATHODE") (pinfunction "C_CATHODE") (pintype "passive"))
      (node (ref "D2") (pin "C") (pinfunction "C_C") (pintype "passive"))
      (node (ref "D5") (pin "C") (pinfunction "C_C") (pintype "passive"))
      (node (ref "U$15") (pin "2") (pinfunction "VIN_2") (pintype "power_in"))
      (node (ref "U$15") (pin "3") (pinfunction "EN_3") (pintype "input"))
    )
    (net (code "137") (name "VDD_SERVO_SENS") (class "Default")
      (node (ref "R918") (pin "P$1") (pinfunction "1_P$1") (pintype "passive"))
      (node (ref "R919") (pin "P$2") (pinfunction "2_P$2") (pintype "passive"))
    )
    (net (code "138") (name "V_EXT") (class "Default")
      (node (ref "D5") (pin "A") (pinfunction "A_A") (pintype "passive"))
      (node (ref "JP5") (pin "1") (pinfunction "1_1") (pintype "passive"))
      (node (ref "R922") (pin "P$2") (pinfunction "2_P$2") (pintype "passive"))
    )
    (net (code "139") (name "V_SERVO") (class "Default")
      (node (ref "D2") (pin "A") (pinfunction "A_A") (pintype "passive"))
      (node (ref "J1") (pin "PWR_S1") (pinfunction "S_PWR_S1") (pintype "passive"))
      (node (ref "J1") (pin "PWR_S2") (pinfunction "S_PWR_S2") (pintype "passive"))
      (node (ref "J1") (pin "PWR_S3") (pinfunction "S_PWR_S3") (pintype "passive"))
      (node (ref "J1") (pin "PWR_S4") (pinfunction "S_PWR_S4") (pintype "passive"))
      (node (ref "J1") (pin "PWR_S5") (pinfunction "S_PWR_S5") (pintype "passive"))
      (node (ref "J1") (pin "PWR_S6") (pinfunction "S_PWR_S6") (pintype "passive"))
      (node (ref "J1") (pin "PWR_S7") (pinfunction "S_PWR_S7") (pintype "passive"))
      (node (ref "J1") (pin "PWR_S8") (pinfunction "S_PWR_S8") (pintype "passive"))
    )
    (net (code "140") (name "unconnected-(J203-4-PadP$4)") (class "Default")
      (node (ref "J203") (pin "P$4") (pinfunction "4_P$4") (pintype "passive"))
    )
    (net (code "141") (name "unconnected-(J203-5-PadP$5)") (class "Default")
      (node (ref "J203") (pin "P$5") (pinfunction "5_P$5") (pintype "passive"))
    )
    (net (code "142") (name "unconnected-(JX301A-S-Pad10)") (class "Default")
      (node (ref "JX301") (pin "10") (pinfunction "S_10") (pintype "passive"))
    )
    (net (code "143") (name "unconnected-(JX301F-S-Pad8)") (class "Default")
      (node (ref "JX301") (pin "8") (pinfunction "S_8") (pintype "passive"))
    )
    (net (code "144") (name "unconnected-(L3-PadP$1)") (class "Default")
      (node (ref "L3") (pin "P$1") (pinfunction "P$1_P$1") (pintype "bidirectional"))
    )
    (net (code "145") (name "unconnected-(L3A-P$2-PadP$16)") (class "Default")
      (node (ref "L3") (pin "P$16") (pinfunction "P$2_P$16") (pintype "bidirectional"))
    )
    (net (code "146") (name "unconnected-(L3B-P$1-PadP$2)") (class "Default")
      (node (ref "L3") (pin "P$2") (pinfunction "P$1_P$2") (pintype "bidirectional"))
    )
    (net (code "147") (name "unconnected-(L3B-P$2-PadP$15)") (class "Default")
      (node (ref "L3") (pin "P$15") (pinfunction "P$2_P$15") (pintype "bidirectional"))
    )
    (net (code "148") (name "unconnected-(L3G-P$1-PadP$7)") (class "Default")
      (node (ref "L3") (pin "P$7") (pinfunction "P$1_P$7") (pintype "bidirectional"))
    )
    (net (code "149") (name "unconnected-(L3G-P$2-PadP$10)") (class "Default")
      (node (ref "L3") (pin "P$10") (pinfunction "P$2_P$10") (pintype "bidirectional"))
    )
    (net (code "150") (name "unconnected-(L3H-P$1-PadP$8)") (class "Default")
      (node (ref "L3") (pin "P$8") (pinfunction "P$1_P$8") (pintype "bidirectional"))
    )
    (net (code "151") (name "unconnected-(L3H-P$2-PadP$9)") (class "Default")
      (node (ref "L3") (pin "P$9") (pinfunction "P$2_P$9") (pintype "bidirectional"))
    )
    (net (code "152") (name "unconnected-(L6C-P$1-PadP$3)") (class "Default")
      (node (ref "L6") (pin "P$3") (pinfunction "P$1_P$3") (pintype "bidirectional"))
    )
    (net (code "153") (name "unconnected-(L6C-P$2-PadP$14)") (class "Default")
      (node (ref "L6") (pin "P$14") (pinfunction "P$2_P$14") (pintype "bidirectional"))
    )
    (net (code "154") (name "unconnected-(L6D-P$1-PadP$4)") (class "Default")
      (node (ref "L6") (pin "P$4") (pinfunction "P$1_P$4") (pintype "bidirectional"))
    )
    (net (code "155") (name "unconnected-(L6D-P$2-PadP$13)") (class "Default")
      (node (ref "L6") (pin "P$13") (pinfunction "P$2_P$13") (pintype "bidirectional"))
    )
    (net (code "156") (name "unconnected-(L6E-P$1-PadP$5)") (class "Default")
      (node (ref "L6") (pin "P$5") (pinfunction "P$1_P$5") (pintype "bidirectional"))
    )
    (net (code "157") (name "unconnected-(L6E-P$2-PadP$12)") (class "Default")
      (node (ref "L6") (pin "P$12") (pinfunction "P$2_P$12") (pintype "bidirectional"))
    )
    (net (code "158") (name "unconnected-(L6F-P$1-PadP$6)") (class "Default")
      (node (ref "L6") (pin "P$6") (pinfunction "P$1_P$6") (pintype "bidirectional"))
    )
    (net (code "159") (name "unconnected-(L6F-P$2-PadP$11)") (class "Default")
      (node (ref "L6") (pin "P$11") (pinfunction "P$2_P$11") (pintype "bidirectional"))
    )
    (net (code "160") (name "unconnected-(U$2-DSYNC-Pad12)") (class "Default")
      (node (ref "U$2") (pin "12") (pinfunction "DSYNC_12") (pintype "bidirectional"))
    )
    (net (code "161") (name "unconnected-(U$2-MST_SCL-Pad2)") (class "Default")
      (node (ref "U$2") (pin "2") (pinfunction "MST_SCL_2") (pintype "bidirectional"))
    )
    (net (code "162") (name "unconnected-(U$2-MST_SDA-Pad3)") (class "Default")
      (node (ref "U$2") (pin "3") (pinfunction "MST_SDA_3") (pintype "bidirectional"))
    )
    (net (code "163") (name "unconnected-(U$2-RSV3-Pad16)") (class "Default")
      (node (ref "U$2") (pin "16") (pinfunction "RSV3_16") (pintype "no_connect"))
    )
    (net (code "164") (name "unconnected-(U$15-FB-Pad12)") (class "Default")
      (node (ref "U$15") (pin "12") (pinfunction "FB_12") (pintype "input"))
    )
    (net (code "165") (name "unconnected-(U$15-PG-Pad5)") (class "Default")
      (node (ref "U$15") (pin "5") (pinfunction "PG_5") (pintype "output"))
    )
    (net (code "166") (name "unconnected-(U101I-PC0-Pad15)") (class "Default")
      (node (ref "U101") (pin "15") (pinfunction "PC0_15") (pintype "bidirectional"))
    )
    (net (code "167") (name "unconnected-(U101I-PC1-Pad16)") (class "Default")
      (node (ref "U101") (pin "16") (pinfunction "PC1_16") (pintype "bidirectional"))
    )
    (net (code "168") (name "unconnected-(U101I-PC2-Pad17)") (class "Default")
      (node (ref "U101") (pin "17") (pinfunction "PC2_17") (pintype "bidirectional"))
    )
    (net (code "169") (name "unconnected-(U101I-PC5-Pad34)") (class "Default")
      (node (ref "U101") (pin "34") (pinfunction "PC5_34") (pintype "bidirectional"))
    )
    (net (code "170") (name "unconnected-(U101I-PC6-Pad63)") (class "Default")
      (node (ref "U101") (pin "63") (pinfunction "PC6_63") (pintype "bidirectional"))
    )
    (net (code "171") (name "unconnected-(U101I-PC7-Pad64)") (class "Default")
      (node (ref "U101") (pin "64") (pinfunction "PC7_64") (pintype "bidirectional"))
    )
    (net (code "172") (name "unconnected-(U101L-PE10-Pad41)") (class "Default")
      (node (ref "U101") (pin "41") (pinfunction "PE10_41") (pintype "bidirectional"))
    )
    (net (code "173") (name "~{ACCEL_MAG_CS}") (class "Default")
      (node (ref "U101") (pin "9") (pinfunction "PC15_9") (pintype "bidirectional"))
    )
    (net (code "174") (name "~{BARO_CS}") (class "Default")
      (node (ref "U101") (pin "88") (pinfunction "PD7_88") (pintype "bidirectional"))
    )
    (net (code "175") (name "~{EX_VDD_5V_VALID}") (class "Default")
      (node (ref "U101") (pin "91") (pinfunction "PB5_91") (pintype "bidirectional"))
    )
    (net (code "176") (name "~{FMU-LED_AMBER}") (class "Default")
      (node (ref "R707") (pin "P$1") (pinfunction "1_P$1") (pintype "passive"))
      (node (ref "U101") (pin "43") (pinfunction "PE12_43") (pintype "bidirectional"))
    )
    (net (code "177") (name "~{FRAM_CS}") (class "Default")
      (node (ref "U101") (pin "57") (pinfunction "PD10_57") (pintype "bidirectional"))
    )
    (net (code "178") (name "~{GYRO_CS}") (class "Default")
      (node (ref "U$2") (pin "8") (pinfunction "CS_8") (pintype "bidirectional"))
      (node (ref "U101") (pin "7") (pinfunction "PC13_7") (pintype "bidirectional"))
    )
    (net (code "179") (name "~{SPI_EXT_NSS}") (class "Default")
      (node (ref "J403") (pin "P$5") (pinfunction "5_P$5") (pintype "passive"))
      (node (ref "U101") (pin "3") (pinfunction "PE4_3") (pintype "bidirectional"))
    )
    (net (code "180") (name "~{VDD_5V_PERIPH_EN}") (class "Default")
      (node (ref "R607") (pin "P$2") (pinfunction "2_P$2") (pintype "passive"))
      (node (ref "U$604") (pin "5") (pinfunction "~{CE}_5") (pintype "bidirectional"))
      (node (ref "U101") (pin "67") (pinfunction "PA8_67") (pintype "bidirectional"))
    )
    (net (code "181") (name "~{VDD_5V_PERIPH_OC}") (class "Default")
      (node (ref "U$604") (pin "4") (pinfunction "~{FAULT}_4") (pintype "bidirectional"))
      (node (ref "U101") (pin "46") (pinfunction "PE15_46") (pintype "bidirectional"))
    )
    (net (code "182") (name "~{VDD_SERVO_VALID}") (class "Default")
      (node (ref "U101") (pin "93") (pinfunction "PB7_93") (pintype "bidirectional"))
    )
  )
)
